# R210I.net
KiCad netlist of a schematic drawn in EAGLE
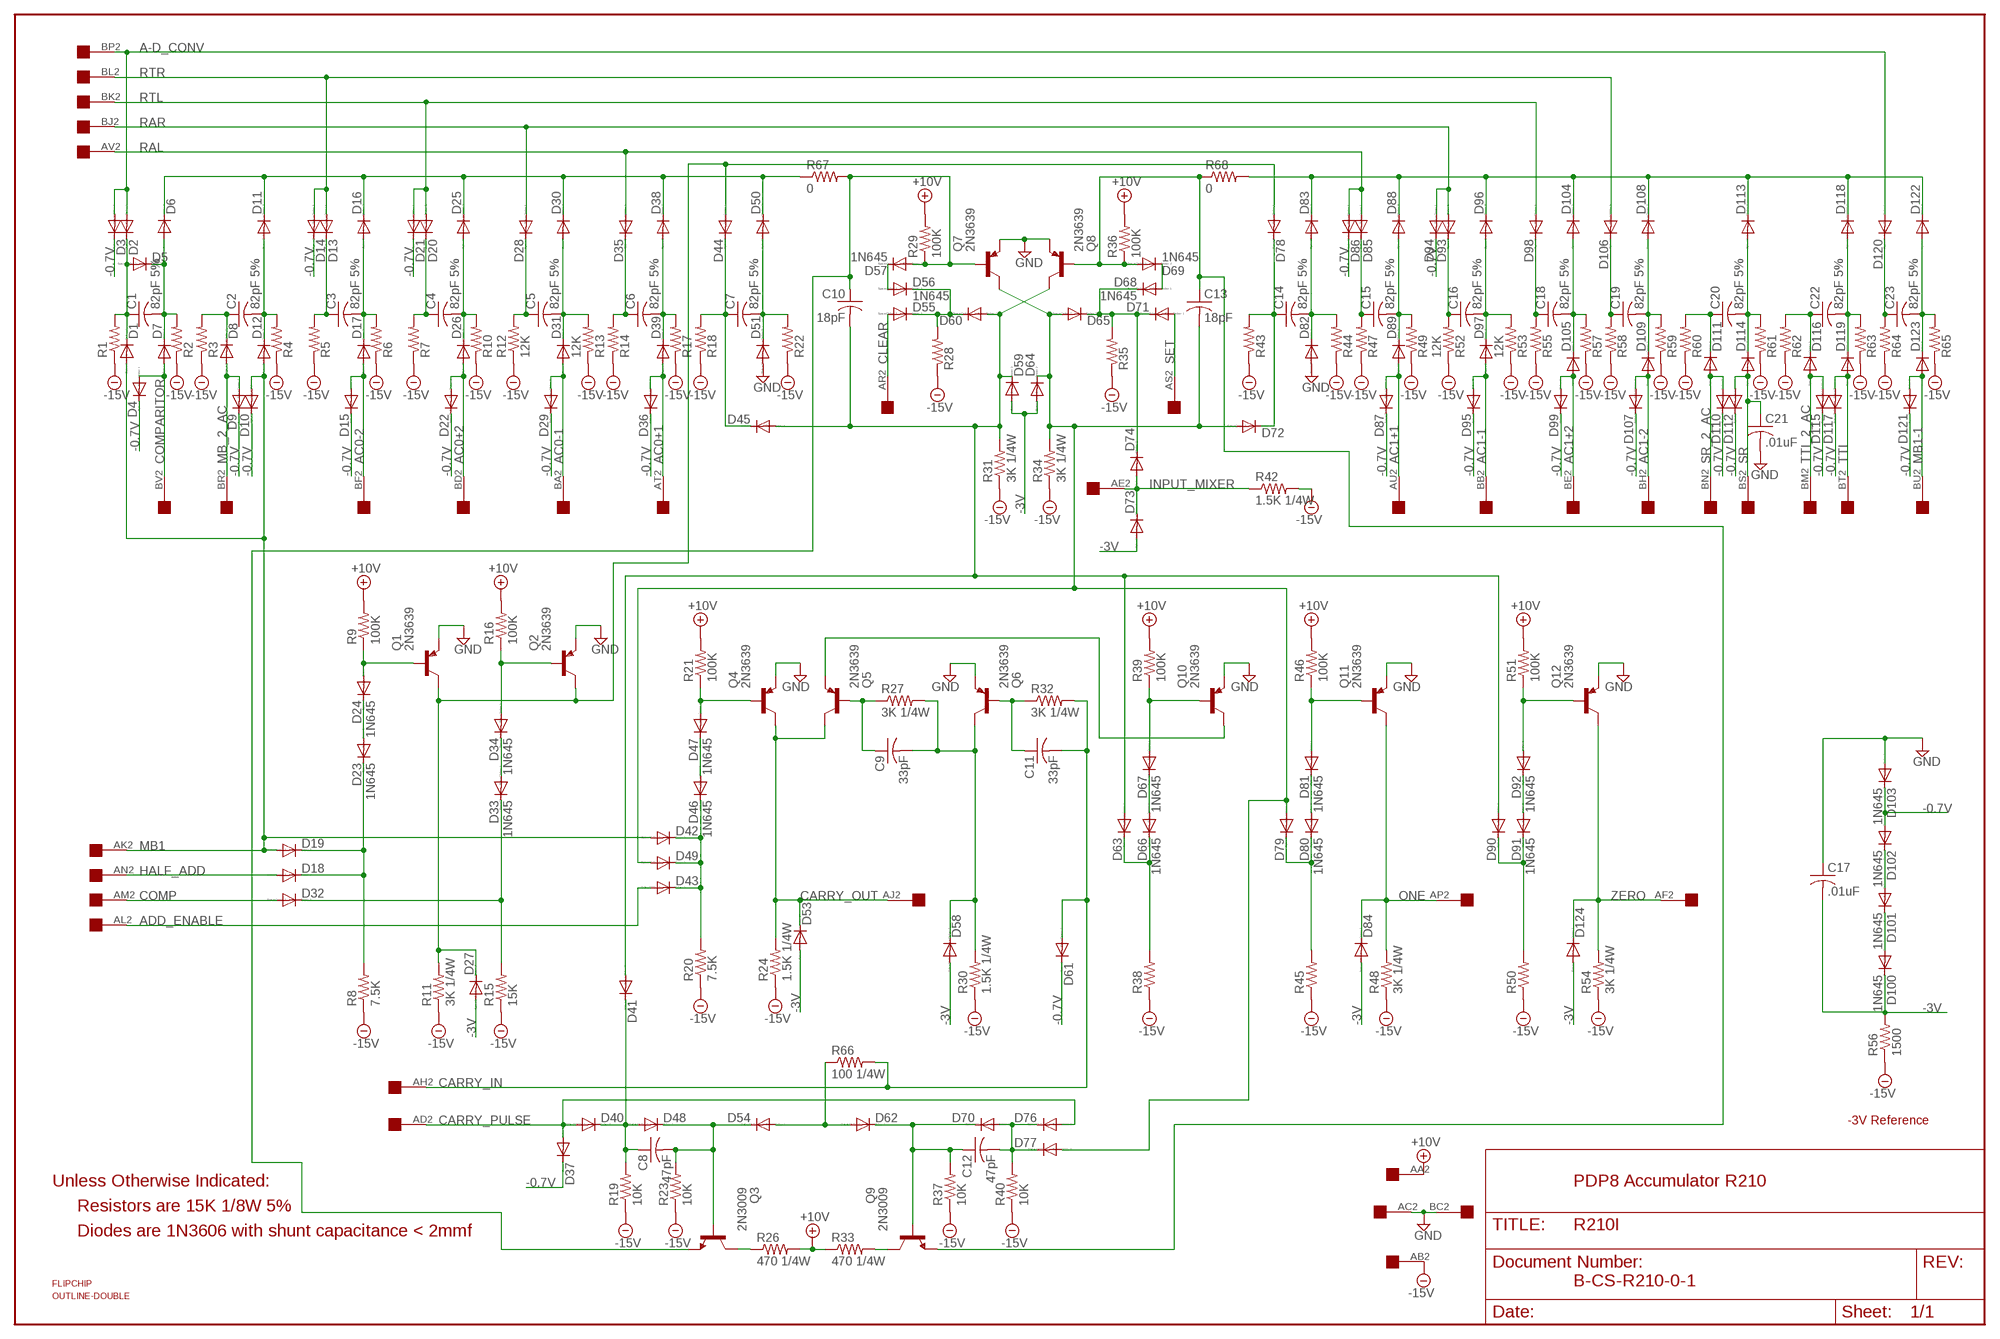
[diagram p0: schematic, sheet 1]

(export (version "E")
  (design (tool "Eeschema 10.0.6"))
  (components
    (comp (ref "C1")
      (value "82pF 5%")
      (footprint "eagle-import:C075-032X103")
      (libsource (lib "eagle-import") (part "C-US075-032X103"))
    )
    (comp (ref "C2")
      (value "82pF 5%")
      (footprint "eagle-import:C075-032X103")
      (libsource (lib "eagle-import") (part "C-US075-032X103"))
    )
    (comp (ref "C3")
      (value "82pF 5%")
      (footprint "eagle-import:C075-032X103")
      (libsource (lib "eagle-import") (part "C-US075-032X103"))
    )
    (comp (ref "C4")
      (value "82pF 5%")
      (footprint "eagle-import:C075-032X103")
      (libsource (lib "eagle-import") (part "C-US075-032X103"))
    )
    (comp (ref "C5")
      (value "82pF 5%")
      (footprint "eagle-import:C075-032X103")
      (libsource (lib "eagle-import") (part "C-US075-032X103"))
    )
    (comp (ref "C6")
      (value "82pF 5%")
      (footprint "eagle-import:C075-032X103")
      (libsource (lib "eagle-import") (part "C-US075-032X103"))
    )
    (comp (ref "C7")
      (value "82pF 5%")
      (footprint "eagle-import:C075-032X103")
      (libsource (lib "eagle-import") (part "C-US075-032X103"))
    )
    (comp (ref "C8")
      (value "47pF")
      (footprint "eagle-import:C075-032X103")
      (libsource (lib "eagle-import") (part "C-US075-032X103"))
    )
    (comp (ref "C9")
      (value "33pF")
      (footprint "eagle-import:C075-032X103")
      (libsource (lib "eagle-import") (part "C-US075-032X103"))
    )
    (comp (ref "C10")
      (value "18pF")
      (footprint "eagle-import:C075-032X103")
      (libsource (lib "eagle-import") (part "C-US075-032X103"))
    )
    (comp (ref "C11")
      (value "33pF")
      (footprint "eagle-import:C075-032X103")
      (libsource (lib "eagle-import") (part "C-US075-032X103"))
    )
    (comp (ref "C12")
      (value "47pF")
      (footprint "eagle-import:C075-032X103")
      (libsource (lib "eagle-import") (part "C-US075-032X103"))
    )
    (comp (ref "C13")
      (value "18pF")
      (footprint "eagle-import:C075-032X103")
      (libsource (lib "eagle-import") (part "C-US075-032X103"))
    )
    (comp (ref "C14")
      (value "82pF 5%")
      (footprint "eagle-import:C075-032X103")
      (libsource (lib "eagle-import") (part "C-US075-032X103"))
    )
    (comp (ref "C15")
      (value "82pF 5%")
      (footprint "eagle-import:C075-032X103")
      (libsource (lib "eagle-import") (part "C-US075-032X103"))
    )
    (comp (ref "C16")
      (value "82pF 5%")
      (footprint "eagle-import:C075-032X103")
      (libsource (lib "eagle-import") (part "C-US075-032X103"))
    )
    (comp (ref "C17")
      (value ".01uF")
      (footprint "eagle-import:C050-025X075")
      (libsource (lib "eagle-import") (part "C-US050-025X075"))
    )
    (comp (ref "C18")
      (value "82pF 5%")
      (footprint "eagle-import:C075-032X103")
      (libsource (lib "eagle-import") (part "C-US075-032X103"))
    )
    (comp (ref "C19")
      (value "82pF 5%")
      (footprint "eagle-import:C075-032X103")
      (libsource (lib "eagle-import") (part "C-US075-032X103"))
    )
    (comp (ref "C20")
      (value "82pF 5%")
      (footprint "eagle-import:C075-032X103")
      (libsource (lib "eagle-import") (part "C-US075-032X103"))
    )
    (comp (ref "C21")
      (value ".01uF")
      (footprint "eagle-import:C050-025X075")
      (libsource (lib "eagle-import") (part "C-US050-025X075"))
    )
    (comp (ref "C22")
      (value "82pF 5%")
      (footprint "eagle-import:C075-032X103")
      (libsource (lib "eagle-import") (part "C-US075-032X103"))
    )
    (comp (ref "C23")
      (value "82pF 5%")
      (footprint "eagle-import:C075-032X103")
      (libsource (lib "eagle-import") (part "C-US075-032X103"))
    )
    (comp (ref "D1")
      (value "1N4148DO35-10")
      (footprint "eagle-import:DO35-10")
      (libsource (lib "eagle-import") (part "1N4148DO35-10"))
    )
    (comp (ref "D2")
      (value "1N4148DO35-10")
      (footprint "eagle-import:DO35-10")
      (libsource (lib "eagle-import") (part "1N4148DO35-10"))
    )
    (comp (ref "D3")
      (value "1N4148DO35-10")
      (footprint "eagle-import:DO35-10")
      (libsource (lib "eagle-import") (part "1N4148DO35-10"))
    )
    (comp (ref "D4")
      (value "1N4148DO35-10")
      (footprint "eagle-import:DO35-10")
      (libsource (lib "eagle-import") (part "1N4148DO35-10"))
    )
    (comp (ref "D5")
      (value "1N4148DO35-10")
      (footprint "eagle-import:DO35-10")
      (libsource (lib "eagle-import") (part "1N4148DO35-10"))
    )
    (comp (ref "D6")
      (value "1N4148DO35-10")
      (footprint "eagle-import:DO35-10")
      (libsource (lib "eagle-import") (part "1N4148DO35-10"))
    )
    (comp (ref "D7")
      (value "1N4148DO35-10")
      (footprint "eagle-import:DO35-10")
      (libsource (lib "eagle-import") (part "1N4148DO35-10"))
    )
    (comp (ref "D8")
      (value "1N4148DO35-10")
      (footprint "eagle-import:DO35-10")
      (libsource (lib "eagle-import") (part "1N4148DO35-10"))
    )
    (comp (ref "D9")
      (value "1N4148DO35-10")
      (footprint "eagle-import:DO35-10")
      (libsource (lib "eagle-import") (part "1N4148DO35-10"))
    )
    (comp (ref "D10")
      (value "1N4148DO35-10")
      (footprint "eagle-import:DO35-10")
      (libsource (lib "eagle-import") (part "1N4148DO35-10"))
    )
    (comp (ref "D11")
      (value "1N4148DO35-10")
      (footprint "eagle-import:DO35-10")
      (libsource (lib "eagle-import") (part "1N4148DO35-10"))
    )
    (comp (ref "D12")
      (value "1N4148DO35-10")
      (footprint "eagle-import:DO35-10")
      (libsource (lib "eagle-import") (part "1N4148DO35-10"))
    )
    (comp (ref "D13")
      (value "1N4148DO35-10")
      (footprint "eagle-import:DO35-10")
      (libsource (lib "eagle-import") (part "1N4148DO35-10"))
    )
    (comp (ref "D14")
      (value "1N4148DO35-10")
      (footprint "eagle-import:DO35-10")
      (libsource (lib "eagle-import") (part "1N4148DO35-10"))
    )
    (comp (ref "D15")
      (value "1N4148DO35-10")
      (footprint "eagle-import:DO35-10")
      (libsource (lib "eagle-import") (part "1N4148DO35-10"))
    )
    (comp (ref "D16")
      (value "1N4148DO35-10")
      (footprint "eagle-import:DO35-10")
      (libsource (lib "eagle-import") (part "1N4148DO35-10"))
    )
    (comp (ref "D17")
      (value "1N4148DO35-10")
      (footprint "eagle-import:DO35-10")
      (libsource (lib "eagle-import") (part "1N4148DO35-10"))
    )
    (comp (ref "D18")
      (value "1N4148DO35-10")
      (footprint "eagle-import:DO35-10")
      (libsource (lib "eagle-import") (part "1N4148DO35-10"))
    )
    (comp (ref "D19")
      (value "1N4148DO35-10")
      (footprint "eagle-import:DO35-10")
      (libsource (lib "eagle-import") (part "1N4148DO35-10"))
    )
    (comp (ref "D20")
      (value "1N4148DO35-10")
      (footprint "eagle-import:DO35-10")
      (libsource (lib "eagle-import") (part "1N4148DO35-10"))
    )
    (comp (ref "D21")
      (value "1N4148DO35-10")
      (footprint "eagle-import:DO35-10")
      (libsource (lib "eagle-import") (part "1N4148DO35-10"))
    )
    (comp (ref "D22")
      (value "1N4148DO35-10")
      (footprint "eagle-import:DO35-10")
      (libsource (lib "eagle-import") (part "1N4148DO35-10"))
    )
    (comp (ref "D23")
      (value "1N645")
      (footprint "eagle-import:DO35-10")
      (libsource (lib "eagle-import") (part "1N4148DO35-10"))
    )
    (comp (ref "D24")
      (value "1N645")
      (footprint "eagle-import:DO35-10")
      (libsource (lib "eagle-import") (part "1N4148DO35-10"))
    )
    (comp (ref "D25")
      (value "1N4148DO35-10")
      (footprint "eagle-import:DO35-10")
      (libsource (lib "eagle-import") (part "1N4148DO35-10"))
    )
    (comp (ref "D26")
      (value "1N4148DO35-10")
      (footprint "eagle-import:DO35-10")
      (libsource (lib "eagle-import") (part "1N4148DO35-10"))
    )
    (comp (ref "D27")
      (value "1N4148DO35-10")
      (footprint "eagle-import:DO35-10")
      (libsource (lib "eagle-import") (part "1N4148DO35-10"))
    )
    (comp (ref "D28")
      (value "1N4148DO35-10")
      (footprint "eagle-import:DO35-10")
      (libsource (lib "eagle-import") (part "1N4148DO35-10"))
    )
    (comp (ref "D29")
      (value "1N4148DO35-10")
      (footprint "eagle-import:DO35-10")
      (libsource (lib "eagle-import") (part "1N4148DO35-10"))
    )
    (comp (ref "D30")
      (value "1N4148DO35-10")
      (footprint "eagle-import:DO35-10")
      (libsource (lib "eagle-import") (part "1N4148DO35-10"))
    )
    (comp (ref "D31")
      (value "1N4148DO35-10")
      (footprint "eagle-import:DO35-10")
      (libsource (lib "eagle-import") (part "1N4148DO35-10"))
    )
    (comp (ref "D32")
      (value "1N4148DO35-10")
      (footprint "eagle-import:DO35-10")
      (libsource (lib "eagle-import") (part "1N4148DO35-10"))
    )
    (comp (ref "D33")
      (value "1N645")
      (footprint "eagle-import:DO35-10")
      (libsource (lib "eagle-import") (part "1N4148DO35-10"))
    )
    (comp (ref "D34")
      (value "1N645")
      (footprint "eagle-import:DO35-10")
      (libsource (lib "eagle-import") (part "1N4148DO35-10"))
    )
    (comp (ref "D35")
      (value "1N4148DO35-10")
      (footprint "eagle-import:DO35-10")
      (libsource (lib "eagle-import") (part "1N4148DO35-10"))
    )
    (comp (ref "D36")
      (value "1N4148DO35-10")
      (footprint "eagle-import:DO35-10")
      (libsource (lib "eagle-import") (part "1N4148DO35-10"))
    )
    (comp (ref "D37")
      (value "1N4148DO35-10")
      (footprint "eagle-import:DO35-10")
      (libsource (lib "eagle-import") (part "1N4148DO35-10"))
    )
    (comp (ref "D38")
      (value "1N4148DO35-10")
      (footprint "eagle-import:DO35-10")
      (libsource (lib "eagle-import") (part "1N4148DO35-10"))
    )
    (comp (ref "D39")
      (value "1N4148DO35-10")
      (footprint "eagle-import:DO35-10")
      (libsource (lib "eagle-import") (part "1N4148DO35-10"))
    )
    (comp (ref "D40")
      (value "1N4148DO35-10")
      (footprint "eagle-import:DO35-10")
      (libsource (lib "eagle-import") (part "1N4148DO35-10"))
    )
    (comp (ref "D41")
      (value "1N4148DO35-10")
      (footprint "eagle-import:DO35-10")
      (libsource (lib "eagle-import") (part "1N4148DO35-10"))
    )
    (comp (ref "D42")
      (value "1N4148DO35-10")
      (footprint "eagle-import:DO35-10")
      (libsource (lib "eagle-import") (part "1N4148DO35-10"))
    )
    (comp (ref "D43")
      (value "1N4148DO35-10")
      (footprint "eagle-import:DO35-10")
      (libsource (lib "eagle-import") (part "1N4148DO35-10"))
    )
    (comp (ref "D44")
      (value "1N4148DO35-10")
      (footprint "eagle-import:DO35-10")
      (libsource (lib "eagle-import") (part "1N4148DO35-10"))
    )
    (comp (ref "D45")
      (value "1N4148DO35-10")
      (footprint "eagle-import:DO35-10")
      (libsource (lib "eagle-import") (part "1N4148DO35-10"))
    )
    (comp (ref "D46")
      (value "1N645")
      (footprint "eagle-import:DO35-10")
      (libsource (lib "eagle-import") (part "1N4148DO35-10"))
    )
    (comp (ref "D47")
      (value "1N645")
      (footprint "eagle-import:DO35-10")
      (libsource (lib "eagle-import") (part "1N4148DO35-10"))
    )
    (comp (ref "D48")
      (value "1N4148DO35-10")
      (footprint "eagle-import:DO35-10")
      (libsource (lib "eagle-import") (part "1N4148DO35-10"))
    )
    (comp (ref "D49")
      (value "1N4148DO35-10")
      (footprint "eagle-import:DO35-10")
      (libsource (lib "eagle-import") (part "1N4148DO35-10"))
    )
    (comp (ref "D50")
      (value "1N4148DO35-10")
      (footprint "eagle-import:DO35-10")
      (libsource (lib "eagle-import") (part "1N4148DO35-10"))
    )
    (comp (ref "D51")
      (value "1N4148DO35-10")
      (footprint "eagle-import:DO35-10")
      (libsource (lib "eagle-import") (part "1N4148DO35-10"))
    )
    (comp (ref "D53")
      (value "1N4148DO35-10")
      (footprint "eagle-import:DO35-10")
      (libsource (lib "eagle-import") (part "1N4148DO35-10"))
    )
    (comp (ref "D54")
      (value "1N4148DO35-10")
      (footprint "eagle-import:DO35-10")
      (libsource (lib "eagle-import") (part "1N4148DO35-10"))
    )
    (comp (ref "D55")
      (value "1N4148DO35-10")
      (footprint "eagle-import:DO35-10")
      (libsource (lib "eagle-import") (part "1N4148DO35-10"))
    )
    (comp (ref "D56")
      (value "1N645")
      (footprint "eagle-import:DO35-10")
      (libsource (lib "eagle-import") (part "1N4148DO35-10"))
    )
    (comp (ref "D57")
      (value "1N645")
      (footprint "eagle-import:DO35-10")
      (libsource (lib "eagle-import") (part "1N4148DO35-10"))
    )
    (comp (ref "D58")
      (value "1N4148DO35-10")
      (footprint "eagle-import:DO35-10")
      (libsource (lib "eagle-import") (part "1N4148DO35-10"))
    )
    (comp (ref "D59")
      (value "1N4148DO35-10")
      (footprint "eagle-import:DO35-10")
      (libsource (lib "eagle-import") (part "1N4148DO35-10"))
    )
    (comp (ref "D60")
      (value "1N4148DO35-10")
      (footprint "eagle-import:DO35-10")
      (libsource (lib "eagle-import") (part "1N4148DO35-10"))
    )
    (comp (ref "D61")
      (value "1N4148DO35-10")
      (footprint "eagle-import:DO35-10")
      (libsource (lib "eagle-import") (part "1N4148DO35-10"))
    )
    (comp (ref "D62")
      (value "1N4148DO35-10")
      (footprint "eagle-import:DO35-10")
      (libsource (lib "eagle-import") (part "1N4148DO35-10"))
    )
    (comp (ref "D63")
      (value "1N4148DO35-10")
      (footprint "eagle-import:DO35-10")
      (libsource (lib "eagle-import") (part "1N4148DO35-10"))
    )
    (comp (ref "D64")
      (value "1N4148DO35-10")
      (footprint "eagle-import:DO35-10")
      (libsource (lib "eagle-import") (part "1N4148DO35-10"))
    )
    (comp (ref "D65")
      (value "1N4148DO35-10")
      (footprint "eagle-import:DO35-10")
      (libsource (lib "eagle-import") (part "1N4148DO35-10"))
    )
    (comp (ref "D66")
      (value "1N645")
      (footprint "eagle-import:DO35-10")
      (libsource (lib "eagle-import") (part "1N4148DO35-10"))
    )
    (comp (ref "D67")
      (value "1N645")
      (footprint "eagle-import:DO35-10")
      (libsource (lib "eagle-import") (part "1N4148DO35-10"))
    )
    (comp (ref "D68")
      (value "1N645")
      (footprint "eagle-import:DO35-10")
      (libsource (lib "eagle-import") (part "1N4148DO35-10"))
    )
    (comp (ref "D69")
      (value "1N645")
      (footprint "eagle-import:DO35-10")
      (libsource (lib "eagle-import") (part "1N4148DO35-10"))
    )
    (comp (ref "D70")
      (value "1N4148DO35-10")
      (footprint "eagle-import:DO35-10")
      (libsource (lib "eagle-import") (part "1N4148DO35-10"))
    )
    (comp (ref "D71")
      (value "1N4148DO35-10")
      (footprint "eagle-import:DO35-10")
      (libsource (lib "eagle-import") (part "1N4148DO35-10"))
    )
    (comp (ref "D72")
      (value "1N4148DO35-10")
      (footprint "eagle-import:DO35-10")
      (libsource (lib "eagle-import") (part "1N4148DO35-10"))
    )
    (comp (ref "D73")
      (value "1N4148DO35-10")
      (footprint "eagle-import:DO35-10")
      (libsource (lib "eagle-import") (part "1N4148DO35-10"))
    )
    (comp (ref "D74")
      (value "1N4148DO35-10")
      (footprint "eagle-import:DO35-10")
      (libsource (lib "eagle-import") (part "1N4148DO35-10"))
    )
    (comp (ref "D76")
      (value "1N4148DO35-10")
      (footprint "eagle-import:DO35-10")
      (libsource (lib "eagle-import") (part "1N4148DO35-10"))
    )
    (comp (ref "D77")
      (value "1N4148DO35-10")
      (footprint "eagle-import:DO35-10")
      (libsource (lib "eagle-import") (part "1N4148DO35-10"))
    )
    (comp (ref "D78")
      (value "1N4148DO35-10")
      (footprint "eagle-import:DO35-10")
      (libsource (lib "eagle-import") (part "1N4148DO35-10"))
    )
    (comp (ref "D79")
      (value "1N4148DO35-10")
      (footprint "eagle-import:DO35-10")
      (libsource (lib "eagle-import") (part "1N4148DO35-10"))
    )
    (comp (ref "D80")
      (value "1N645")
      (footprint "eagle-import:DO35-10")
      (libsource (lib "eagle-import") (part "1N4148DO35-10"))
    )
    (comp (ref "D81")
      (value "1N645")
      (footprint "eagle-import:DO35-10")
      (libsource (lib "eagle-import") (part "1N4148DO35-10"))
    )
    (comp (ref "D82")
      (value "1N4148DO35-10")
      (footprint "eagle-import:DO35-10")
      (libsource (lib "eagle-import") (part "1N4148DO35-10"))
    )
    (comp (ref "D83")
      (value "1N4148DO35-10")
      (footprint "eagle-import:DO35-10")
      (libsource (lib "eagle-import") (part "1N4148DO35-10"))
    )
    (comp (ref "D84")
      (value "1N4148DO35-10")
      (footprint "eagle-import:DO35-10")
      (libsource (lib "eagle-import") (part "1N4148DO35-10"))
    )
    (comp (ref "D85")
      (value "1N4148DO35-10")
      (footprint "eagle-import:DO35-10")
      (libsource (lib "eagle-import") (part "1N4148DO35-10"))
    )
    (comp (ref "D86")
      (value "1N4148DO35-10")
      (footprint "eagle-import:DO35-10")
      (libsource (lib "eagle-import") (part "1N4148DO35-10"))
    )
    (comp (ref "D87")
      (value "1N4148DO35-10")
      (footprint "eagle-import:DO35-10")
      (libsource (lib "eagle-import") (part "1N4148DO35-10"))
    )
    (comp (ref "D88")
      (value "1N4148DO35-10")
      (footprint "eagle-import:DO35-10")
      (libsource (lib "eagle-import") (part "1N4148DO35-10"))
    )
    (comp (ref "D89")
      (value "1N4148DO35-10")
      (footprint "eagle-import:DO35-10")
      (libsource (lib "eagle-import") (part "1N4148DO35-10"))
    )
    (comp (ref "D90")
      (value "1N4148DO35-10")
      (footprint "eagle-import:DO35-10")
      (libsource (lib "eagle-import") (part "1N4148DO35-10"))
    )
    (comp (ref "D91")
      (value "1N645")
      (footprint "eagle-import:DO35-10")
      (libsource (lib "eagle-import") (part "1N4148DO35-10"))
    )
    (comp (ref "D92")
      (value "1N645")
      (footprint "eagle-import:DO35-10")
      (libsource (lib "eagle-import") (part "1N4148DO35-10"))
    )
    (comp (ref "D93")
      (value "1N4148DO35-10")
      (footprint "eagle-import:DO35-10")
      (libsource (lib "eagle-import") (part "1N4148DO35-10"))
    )
    (comp (ref "D94")
      (value "1N4148DO35-10")
      (footprint "eagle-import:DO35-10")
      (libsource (lib "eagle-import") (part "1N4148DO35-10"))
    )
    (comp (ref "D95")
      (value "1N4148DO35-10")
      (footprint "eagle-import:DO35-10")
      (libsource (lib "eagle-import") (part "1N4148DO35-10"))
    )
    (comp (ref "D96")
      (value "1N4148DO35-10")
      (footprint "eagle-import:DO35-10")
      (libsource (lib "eagle-import") (part "1N4148DO35-10"))
    )
    (comp (ref "D97")
      (value "1N4148DO35-10")
      (footprint "eagle-import:DO35-10")
      (libsource (lib "eagle-import") (part "1N4148DO35-10"))
    )
    (comp (ref "D98")
      (value "1N4148DO35-10")
      (footprint "eagle-import:DO35-10")
      (libsource (lib "eagle-import") (part "1N4148DO35-10"))
    )
    (comp (ref "D99")
      (value "1N4148DO35-10")
      (footprint "eagle-import:DO35-10")
      (libsource (lib "eagle-import") (part "1N4148DO35-10"))
    )
    (comp (ref "D100")
      (value "1N645")
      (footprint "eagle-import:DO35-10")
      (libsource (lib "eagle-import") (part "1N4148DO35-10"))
    )
    (comp (ref "D101")
      (value "1N645")
      (footprint "eagle-import:DO35-10")
      (libsource (lib "eagle-import") (part "1N4148DO35-10"))
    )
    (comp (ref "D102")
      (value "1N645")
      (footprint "eagle-import:DO35-10")
      (libsource (lib "eagle-import") (part "1N4148DO35-10"))
    )
    (comp (ref "D103")
      (value "1N645")
      (footprint "eagle-import:DO35-10")
      (libsource (lib "eagle-import") (part "1N4148DO35-10"))
    )
    (comp (ref "D104")
      (value "1N4148DO35-10")
      (footprint "eagle-import:DO35-10")
      (libsource (lib "eagle-import") (part "1N4148DO35-10"))
    )
    (comp (ref "D105")
      (value "1N4148DO35-10")
      (footprint "eagle-import:DO35-10")
      (libsource (lib "eagle-import") (part "1N4148DO35-10"))
    )
    (comp (ref "D106")
      (value "1N4148DO35-10")
      (footprint "eagle-import:DO35-10")
      (libsource (lib "eagle-import") (part "1N4148DO35-10"))
    )
    (comp (ref "D107")
      (value "1N4148DO35-10")
      (footprint "eagle-import:DO35-10")
      (libsource (lib "eagle-import") (part "1N4148DO35-10"))
    )
    (comp (ref "D108")
      (value "1N4148DO35-10")
      (footprint "eagle-import:DO35-10")
      (libsource (lib "eagle-import") (part "1N4148DO35-10"))
    )
    (comp (ref "D109")
      (value "1N4148DO35-10")
      (footprint "eagle-import:DO35-10")
      (libsource (lib "eagle-import") (part "1N4148DO35-10"))
    )
    (comp (ref "D110")
      (value "1N4148DO35-10")
      (footprint "eagle-import:DO35-10")
      (libsource (lib "eagle-import") (part "1N4148DO35-10"))
    )
    (comp (ref "D111")
      (value "1N4148DO35-10")
      (footprint "eagle-import:DO35-10")
      (libsource (lib "eagle-import") (part "1N4148DO35-10"))
    )
    (comp (ref "D112")
      (value "1N4148DO35-10")
      (footprint "eagle-import:DO35-10")
      (libsource (lib "eagle-import") (part "1N4148DO35-10"))
    )
    (comp (ref "D113")
      (value "1N4148DO35-10")
      (footprint "eagle-import:DO35-10")
      (libsource (lib "eagle-import") (part "1N4148DO35-10"))
    )
    (comp (ref "D114")
      (value "1N4148DO35-10")
      (footprint "eagle-import:DO35-10")
      (libsource (lib "eagle-import") (part "1N4148DO35-10"))
    )
    (comp (ref "D115")
      (value "1N4148DO35-10")
      (footprint "eagle-import:DO35-10")
      (libsource (lib "eagle-import") (part "1N4148DO35-10"))
    )
    (comp (ref "D116")
      (value "1N4148DO35-10")
      (footprint "eagle-import:DO35-10")
      (libsource (lib "eagle-import") (part "1N4148DO35-10"))
    )
    (comp (ref "D117")
      (value "1N4148DO35-10")
      (footprint "eagle-import:DO35-10")
      (libsource (lib "eagle-import") (part "1N4148DO35-10"))
    )
    (comp (ref "D118")
      (value "1N4148DO35-10")
      (footprint "eagle-import:DO35-10")
      (libsource (lib "eagle-import") (part "1N4148DO35-10"))
    )
    (comp (ref "D119")
      (value "1N4148DO35-10")
      (footprint "eagle-import:DO35-10")
      (libsource (lib "eagle-import") (part "1N4148DO35-10"))
    )
    (comp (ref "D120")
      (value "1N4148DO35-10")
      (footprint "eagle-import:DO35-10")
      (libsource (lib "eagle-import") (part "1N4148DO35-10"))
    )
    (comp (ref "D121")
      (value "1N4148DO35-10")
      (footprint "eagle-import:DO35-10")
      (libsource (lib "eagle-import") (part "1N4148DO35-10"))
    )
    (comp (ref "D122")
      (value "1N4148DO35-10")
      (footprint "eagle-import:DO35-10")
      (libsource (lib "eagle-import") (part "1N4148DO35-10"))
    )
    (comp (ref "D123")
      (value "1N4148DO35-10")
      (footprint "eagle-import:DO35-10")
      (libsource (lib "eagle-import") (part "1N4148DO35-10"))
    )
    (comp (ref "D124")
      (value "1N4148DO35-10")
      (footprint "eagle-import:DO35-10")
      (libsource (lib "eagle-import") (part "1N4148DO35-10"))
    )
    (comp (ref "Q1")
      (value "2N3639")
      (footprint "eagle-import:TO39")
      (libsource (lib "eagle-import") (part "2N3637"))
    )
    (comp (ref "Q2")
      (value "2N3639")
      (footprint "eagle-import:TO39")
      (libsource (lib "eagle-import") (part "2N3637"))
    )
    (comp (ref "Q3")
      (value "2N3009")
      (footprint "eagle-import:TO5")
      (libsource (lib "eagle-import") (part "2N2102"))
    )
    (comp (ref "Q4")
      (value "2N3639")
      (footprint "eagle-import:TO39")
      (libsource (lib "eagle-import") (part "2N3637"))
    )
    (comp (ref "Q5")
      (value "2N3639")
      (footprint "eagle-import:TO39")
      (libsource (lib "eagle-import") (part "2N3637"))
    )
    (comp (ref "Q6")
      (value "2N3639")
      (footprint "eagle-import:TO39")
      (libsource (lib "eagle-import") (part "2N3637"))
    )
    (comp (ref "Q7")
      (value "2N3639")
      (footprint "eagle-import:TO39")
      (libsource (lib "eagle-import") (part "2N3637"))
    )
    (comp (ref "Q8")
      (value "2N3639")
      (footprint "eagle-import:TO39")
      (libsource (lib "eagle-import") (part "2N3637"))
    )
    (comp (ref "Q9")
      (value "2N3009")
      (footprint "eagle-import:TO5")
      (libsource (lib "eagle-import") (part "2N2102"))
    )
    (comp (ref "Q10")
      (value "2N3639")
      (footprint "eagle-import:TO39")
      (libsource (lib "eagle-import") (part "2N3637"))
    )
    (comp (ref "Q11")
      (value "2N3639")
      (footprint "eagle-import:TO39")
      (libsource (lib "eagle-import") (part "2N3637"))
    )
    (comp (ref "Q12")
      (value "2N3639")
      (footprint "eagle-import:TO39")
      (libsource (lib "eagle-import") (part "2N3637"))
    )
    (comp (ref "R1")
      (value "R-US_0207/10")
      (footprint "eagle-import:0207_10")
      (libsource (lib "eagle-import") (part "R-US_0207/10"))
    )
    (comp (ref "R2")
      (value "R-US_0207/10")
      (footprint "eagle-import:0207_10")
      (libsource (lib "eagle-import") (part "R-US_0207/10"))
    )
    (comp (ref "R3")
      (value "R-US_0207/10")
      (footprint "eagle-import:0207_10")
      (libsource (lib "eagle-import") (part "R-US_0207/10"))
    )
    (comp (ref "R4")
      (value "R-US_0207/10")
      (footprint "eagle-import:0207_10")
      (libsource (lib "eagle-import") (part "R-US_0207/10"))
    )
    (comp (ref "R5")
      (value "R-US_0207/10")
      (footprint "eagle-import:0207_10")
      (libsource (lib "eagle-import") (part "R-US_0207/10"))
    )
    (comp (ref "R6")
      (value "R-US_0207/10")
      (footprint "eagle-import:0207_10")
      (libsource (lib "eagle-import") (part "R-US_0207/10"))
    )
    (comp (ref "R7")
      (value "R-US_0207/10")
      (footprint "eagle-import:0207_10")
      (libsource (lib "eagle-import") (part "R-US_0207/10"))
    )
    (comp (ref "R8")
      (value "7.5K")
      (footprint "eagle-import:0207_10")
      (libsource (lib "eagle-import") (part "R-US_0207/10"))
    )
    (comp (ref "R9")
      (value "100K")
      (footprint "eagle-import:0207_10")
      (libsource (lib "eagle-import") (part "R-US_0207/10"))
    )
    (comp (ref "R10")
      (value "R-US_0207/10")
      (footprint "eagle-import:0207_10")
      (libsource (lib "eagle-import") (part "R-US_0207/10"))
    )
    (comp (ref "R11")
      (value "3K 1/4W")
      (footprint "eagle-import:0207_10")
      (libsource (lib "eagle-import") (part "R-US_0207/10"))
    )
    (comp (ref "R12")
      (value "12K")
      (footprint "eagle-import:0207_10")
      (libsource (lib "eagle-import") (part "R-US_0207/10"))
    )
    (comp (ref "R13")
      (value "12K")
      (footprint "eagle-import:0207_10")
      (libsource (lib "eagle-import") (part "R-US_0207/10"))
    )
    (comp (ref "R14")
      (value "R-US_0207/10")
      (footprint "eagle-import:0207_10")
      (libsource (lib "eagle-import") (part "R-US_0207/10"))
    )
    (comp (ref "R15")
      (value "15K")
      (footprint "eagle-import:0207_10")
      (libsource (lib "eagle-import") (part "R-US_0207/10"))
    )
    (comp (ref "R16")
      (value "100K")
      (footprint "eagle-import:0207_10")
      (libsource (lib "eagle-import") (part "R-US_0207/10"))
    )
    (comp (ref "R17")
      (value "R-US_0207/10")
      (footprint "eagle-import:0207_10")
      (libsource (lib "eagle-import") (part "R-US_0207/10"))
    )
    (comp (ref "R18")
      (value "R-US_0207/10")
      (footprint "eagle-import:0207_10")
      (libsource (lib "eagle-import") (part "R-US_0207/10"))
    )
    (comp (ref "R19")
      (value "10K")
      (footprint "eagle-import:0207_10")
      (libsource (lib "eagle-import") (part "R-US_0207/10"))
    )
    (comp (ref "R20")
      (value "7.5K")
      (footprint "eagle-import:0207_10")
      (libsource (lib "eagle-import") (part "R-US_0207/10"))
    )
    (comp (ref "R21")
      (value "100K")
      (footprint "eagle-import:0207_10")
      (libsource (lib "eagle-import") (part "R-US_0207/10"))
    )
    (comp (ref "R22")
      (value "R-US_0207/10")
      (footprint "eagle-import:0207_10")
      (libsource (lib "eagle-import") (part "R-US_0207/10"))
    )
    (comp (ref "R23")
      (value "10K")
      (footprint "eagle-import:0207_10")
      (libsource (lib "eagle-import") (part "R-US_0207/10"))
    )
    (comp (ref "R24")
      (value "1.5K 1/4W")
      (footprint "eagle-import:0207_10")
      (libsource (lib "eagle-import") (part "R-US_0207/10"))
    )
    (comp (ref "R26")
      (value "470 1/4W")
      (footprint "eagle-import:0207_10")
      (libsource (lib "eagle-import") (part "R-US_0207/10"))
    )
    (comp (ref "R27")
      (value "3K 1/4W")
      (footprint "eagle-import:0207_10")
      (libsource (lib "eagle-import") (part "R-US_0207/10"))
    )
    (comp (ref "R28")
      (value "R-US_0207/10")
      (footprint "eagle-import:0207_10")
      (libsource (lib "eagle-import") (part "R-US_0207/10"))
    )
    (comp (ref "R29")
      (value "100K")
      (footprint "eagle-import:0207_10")
      (libsource (lib "eagle-import") (part "R-US_0207/10"))
    )
    (comp (ref "R30")
      (value "1.5K 1/4W")
      (footprint "eagle-import:0207_10")
      (libsource (lib "eagle-import") (part "R-US_0207/10"))
    )
    (comp (ref "R31")
      (value "3K 1/4W")
      (footprint "eagle-import:0207_10")
      (libsource (lib "eagle-import") (part "R-US_0207/10"))
    )
    (comp (ref "R32")
      (value "3K 1/4W")
      (footprint "eagle-import:0207_10")
      (libsource (lib "eagle-import") (part "R-US_0207/10"))
    )
    (comp (ref "R33")
      (value "470 1/4W")
      (footprint "eagle-import:0207_10")
      (libsource (lib "eagle-import") (part "R-US_0207/10"))
    )
    (comp (ref "R34")
      (value "3K 1/4W")
      (footprint "eagle-import:0207_10")
      (libsource (lib "eagle-import") (part "R-US_0207/10"))
    )
    (comp (ref "R35")
      (value "R-US_0207/10")
      (footprint "eagle-import:0207_10")
      (libsource (lib "eagle-import") (part "R-US_0207/10"))
    )
    (comp (ref "R36")
      (value "100K")
      (footprint "eagle-import:0207_10")
      (libsource (lib "eagle-import") (part "R-US_0207/10"))
    )
    (comp (ref "R37")
      (value "10K")
      (footprint "eagle-import:0207_10")
      (libsource (lib "eagle-import") (part "R-US_0207/10"))
    )
    (comp (ref "R38")
      (value "R-US_0207/10")
      (footprint "eagle-import:0207_10")
      (libsource (lib "eagle-import") (part "R-US_0207/10"))
    )
    (comp (ref "R39")
      (value "100K")
      (footprint "eagle-import:0207_10")
      (libsource (lib "eagle-import") (part "R-US_0207/10"))
    )
    (comp (ref "R40")
      (value "10K")
      (footprint "eagle-import:0207_10")
      (libsource (lib "eagle-import") (part "R-US_0207/10"))
    )
    (comp (ref "R42")
      (value "1.5K 1/4W")
      (footprint "eagle-import:0207_10")
      (libsource (lib "eagle-import") (part "R-US_0207/10"))
    )
    (comp (ref "R43")
      (value "R-US_0207/10")
      (footprint "eagle-import:0207_10")
      (libsource (lib "eagle-import") (part "R-US_0207/10"))
    )
    (comp (ref "R44")
      (value "R-US_0207/10")
      (footprint "eagle-import:0207_10")
      (libsource (lib "eagle-import") (part "R-US_0207/10"))
    )
    (comp (ref "R45")
      (value "R-US_0207/10")
      (footprint "eagle-import:0207_10")
      (libsource (lib "eagle-import") (part "R-US_0207/10"))
    )
    (comp (ref "R46")
      (value "100K")
      (footprint "eagle-import:0207_10")
      (libsource (lib "eagle-import") (part "R-US_0207/10"))
    )
    (comp (ref "R47")
      (value "R-US_0207/10")
      (footprint "eagle-import:0207_10")
      (libsource (lib "eagle-import") (part "R-US_0207/10"))
    )
    (comp (ref "R48")
      (value "3K 1/4W")
      (footprint "eagle-import:0207_10")
      (libsource (lib "eagle-import") (part "R-US_0207/10"))
    )
    (comp (ref "R49")
      (value "R-US_0207/10")
      (footprint "eagle-import:0207_10")
      (libsource (lib "eagle-import") (part "R-US_0207/10"))
    )
    (comp (ref "R50")
      (value "R-US_0207/10")
      (footprint "eagle-import:0207_10")
      (libsource (lib "eagle-import") (part "R-US_0207/10"))
    )
    (comp (ref "R51")
      (value "100K")
      (footprint "eagle-import:0207_10")
      (libsource (lib "eagle-import") (part "R-US_0207/10"))
    )
    (comp (ref "R52")
      (value "12K")
      (footprint "eagle-import:0207_10")
      (libsource (lib "eagle-import") (part "R-US_0207/10"))
    )
    (comp (ref "R53")
      (value "12K")
      (footprint "eagle-import:0207_10")
      (libsource (lib "eagle-import") (part "R-US_0207/10"))
    )
    (comp (ref "R54")
      (value "3K 1/4W")
      (footprint "eagle-import:0207_10")
      (libsource (lib "eagle-import") (part "R-US_0207/10"))
    )
    (comp (ref "R55")
      (value "R-US_0207/10")
      (footprint "eagle-import:0207_10")
      (libsource (lib "eagle-import") (part "R-US_0207/10"))
    )
    (comp (ref "R56")
      (value "1500")
      (footprint "eagle-import:0207_10")
      (libsource (lib "eagle-import") (part "R-US_0207/10"))
    )
    (comp (ref "R57")
      (value "R-US_0207/10")
      (footprint "eagle-import:0207_10")
      (libsource (lib "eagle-import") (part "R-US_0207/10"))
    )
    (comp (ref "R58")
      (value "R-US_0207/10")
      (footprint "eagle-import:0207_10")
      (libsource (lib "eagle-import") (part "R-US_0207/10"))
    )
    (comp (ref "R59")
      (value "R-US_0207/10")
      (footprint "eagle-import:0207_10")
      (libsource (lib "eagle-import") (part "R-US_0207/10"))
    )
    (comp (ref "R60")
      (value "R-US_0207/10")
      (footprint "eagle-import:0207_10")
      (libsource (lib "eagle-import") (part "R-US_0207/10"))
    )
    (comp (ref "R61")
      (value "R-US_0207/10")
      (footprint "eagle-import:0207_10")
      (libsource (lib "eagle-import") (part "R-US_0207/10"))
    )
    (comp (ref "R62")
      (value "R-US_0207/10")
      (footprint "eagle-import:0207_10")
      (libsource (lib "eagle-import") (part "R-US_0207/10"))
    )
    (comp (ref "R63")
      (value "R-US_0207/10")
      (footprint "eagle-import:0207_10")
      (libsource (lib "eagle-import") (part "R-US_0207/10"))
    )
    (comp (ref "R64")
      (value "R-US_0207/10")
      (footprint "eagle-import:0207_10")
      (libsource (lib "eagle-import") (part "R-US_0207/10"))
    )
    (comp (ref "R65")
      (value "R-US_0207/10")
      (footprint "eagle-import:0207_10")
      (libsource (lib "eagle-import") (part "R-US_0207/10"))
    )
    (comp (ref "R66")
      (value "100 1/4W")
      (footprint "eagle-import:0207_10")
      (libsource (lib "eagle-import") (part "R-US_0207/10"))
    )
    (comp (ref "R67")
      (value "0")
      (footprint "eagle-import:0207_10")
      (libsource (lib "eagle-import") (part "R-US_0207/10"))
    )
    (comp (ref "R68")
      (value "0")
      (footprint "eagle-import:0207_10")
      (libsource (lib "eagle-import") (part "R-US_0207/10"))
    )
    (comp (ref "U$1")
      (value "DOUBLE")
      (footprint "eagle-import:EDGE-CON4")
      (libsource (lib "eagle-import") (part "DOUBLE"))
    )
    (comp (ref "U$2")
      (value "FLIPCHIP")
      (footprint "eagle-import:FLIPCHIP")
      (libsource (lib "eagle-import") (part "FLIPCHIP"))
    )
    (comp (ref "U$3")
      (value "OUTLINE-DOUBLE")
      (footprint "eagle-import:DOUBLE")
      (libsource (lib "eagle-import") (part "OUTLINE-DOUBLE"))
    )
  )
  (nets
    (net (code "1") (name "+10V") (class "Default")
      (node (ref "R16") (pin "2") (pinfunction "2_2") (pintype "passive"))
      (node (ref "R21") (pin "2") (pinfunction "2_2") (pintype "passive"))
      (node (ref "R26") (pin "2") (pinfunction "2_2") (pintype "passive"))
      (node (ref "R29") (pin "2") (pinfunction "2_2") (pintype "passive"))
      (node (ref "R33") (pin "1") (pinfunction "1_1") (pintype "passive"))
      (node (ref "R36") (pin "2") (pinfunction "2_2") (pintype "passive"))
      (node (ref "R39") (pin "2") (pinfunction "2_2") (pintype "passive"))
      (node (ref "R46") (pin "2") (pinfunction "2_2") (pintype "passive"))
      (node (ref "R51") (pin "2") (pinfunction "2_2") (pintype "passive"))
      (node (ref "R9") (pin "2") (pinfunction "2_2") (pintype "passive"))
      (node (ref "U$1") (pin "AA2") (pinfunction "1_AA2") (pintype "bidirectional"))
    )
    (net (code "2") (name "-15V") (class "Default")
      (node (ref "R1") (pin "1") (pinfunction "1_1") (pintype "passive"))
      (node (ref "R10") (pin "1") (pinfunction "1_1") (pintype "passive"))
      (node (ref "R11") (pin "1") (pinfunction "1_1") (pintype "passive"))
      (node (ref "R12") (pin "1") (pinfunction "1_1") (pintype "passive"))
      (node (ref "R13") (pin "1") (pinfunction "1_1") (pintype "passive"))
      (node (ref "R14") (pin "1") (pinfunction "1_1") (pintype "passive"))
      (node (ref "R15") (pin "1") (pinfunction "1_1") (pintype "passive"))
      (node (ref "R17") (pin "1") (pinfunction "1_1") (pintype "passive"))
      (node (ref "R18") (pin "1") (pinfunction "1_1") (pintype "passive"))
      (node (ref "R19") (pin "1") (pinfunction "1_1") (pintype "passive"))
      (node (ref "R2") (pin "1") (pinfunction "1_1") (pintype "passive"))
      (node (ref "R20") (pin "1") (pinfunction "1_1") (pintype "passive"))
      (node (ref "R22") (pin "1") (pinfunction "1_1") (pintype "passive"))
      (node (ref "R23") (pin "1") (pinfunction "1_1") (pintype "passive"))
      (node (ref "R24") (pin "1") (pinfunction "1_1") (pintype "passive"))
      (node (ref "R28") (pin "1") (pinfunction "1_1") (pintype "passive"))
      (node (ref "R3") (pin "1") (pinfunction "1_1") (pintype "passive"))
      (node (ref "R30") (pin "1") (pinfunction "1_1") (pintype "passive"))
      (node (ref "R31") (pin "1") (pinfunction "1_1") (pintype "passive"))
      (node (ref "R34") (pin "1") (pinfunction "1_1") (pintype "passive"))
      (node (ref "R35") (pin "1") (pinfunction "1_1") (pintype "passive"))
      (node (ref "R37") (pin "1") (pinfunction "1_1") (pintype "passive"))
      (node (ref "R38") (pin "1") (pinfunction "1_1") (pintype "passive"))
      (node (ref "R4") (pin "1") (pinfunction "1_1") (pintype "passive"))
      (node (ref "R40") (pin "1") (pinfunction "1_1") (pintype "passive"))
      (node (ref "R42") (pin "2") (pinfunction "2_2") (pintype "passive"))
      (node (ref "R43") (pin "1") (pinfunction "1_1") (pintype "passive"))
      (node (ref "R44") (pin "1") (pinfunction "1_1") (pintype "passive"))
      (node (ref "R45") (pin "1") (pinfunction "1_1") (pintype "passive"))
      (node (ref "R47") (pin "1") (pinfunction "1_1") (pintype "passive"))
      (node (ref "R48") (pin "1") (pinfunction "1_1") (pintype "passive"))
      (node (ref "R49") (pin "1") (pinfunction "1_1") (pintype "passive"))
      (node (ref "R5") (pin "1") (pinfunction "1_1") (pintype "passive"))
      (node (ref "R50") (pin "1") (pinfunction "1_1") (pintype "passive"))
      (node (ref "R52") (pin "1") (pinfunction "1_1") (pintype "passive"))
      (node (ref "R53") (pin "1") (pinfunction "1_1") (pintype "passive"))
      (node (ref "R54") (pin "1") (pinfunction "1_1") (pintype "passive"))
      (node (ref "R55") (pin "1") (pinfunction "1_1") (pintype "passive"))
      (node (ref "R56") (pin "1") (pinfunction "1_1") (pintype "passive"))
      (node (ref "R57") (pin "1") (pinfunction "1_1") (pintype "passive"))
      (node (ref "R58") (pin "1") (pinfunction "1_1") (pintype "passive"))
      (node (ref "R59") (pin "1") (pinfunction "1_1") (pintype "passive"))
      (node (ref "R6") (pin "1") (pinfunction "1_1") (pintype "passive"))
      (node (ref "R60") (pin "1") (pinfunction "1_1") (pintype "passive"))
      (node (ref "R61") (pin "1") (pinfunction "1_1") (pintype "passive"))
      (node (ref "R62") (pin "1") (pinfunction "1_1") (pintype "passive"))
      (node (ref "R63") (pin "1") (pinfunction "1_1") (pintype "passive"))
      (node (ref "R64") (pin "1") (pinfunction "1_1") (pintype "passive"))
      (node (ref "R65") (pin "1") (pinfunction "1_1") (pintype "passive"))
      (node (ref "R7") (pin "1") (pinfunction "1_1") (pintype "passive"))
      (node (ref "R8") (pin "1") (pinfunction "1_1") (pintype "passive"))
      (node (ref "U$1") (pin "AB2") (pinfunction "1_AB2") (pintype "bidirectional"))
    )
    (net (code "3") (name "/-0.7V") (class "Default")
      (node (ref "D10") (pin "C") (pinfunction "C_C") (pintype "passive"))
      (node (ref "D102") (pin "A") (pinfunction "A_A") (pintype "passive"))
      (node (ref "D103") (pin "C") (pinfunction "C_C") (pintype "passive"))
      (node (ref "D107") (pin "C") (pinfunction "C_C") (pintype "passive"))
      (node (ref "D110") (pin "C") (pinfunction "C_C") (pintype "passive"))
      (node (ref "D112") (pin "C") (pinfunction "C_C") (pintype "passive"))
      (node (ref "D115") (pin "C") (pinfunction "C_C") (pintype "passive"))
      (node (ref "D117") (pin "C") (pinfunction "C_C") (pintype "passive"))
      (node (ref "D121") (pin "C") (pinfunction "C_C") (pintype "passive"))
      (node (ref "D14") (pin "C") (pinfunction "C_C") (pintype "passive"))
      (node (ref "D15") (pin "C") (pinfunction "C_C") (pintype "passive"))
      (node (ref "D21") (pin "C") (pinfunction "C_C") (pintype "passive"))
      (node (ref "D22") (pin "C") (pinfunction "C_C") (pintype "passive"))
      (node (ref "D29") (pin "C") (pinfunction "C_C") (pintype "passive"))
      (node (ref "D3") (pin "C") (pinfunction "C_C") (pintype "passive"))
      (node (ref "D36") (pin "C") (pinfunction "C_C") (pintype "passive"))
      (node (ref "D37") (pin "C") (pinfunction "C_C") (pintype "passive"))
      (node (ref "D4") (pin "C") (pinfunction "C_C") (pintype "passive"))
      (node (ref "D61") (pin "C") (pinfunction "C_C") (pintype "passive"))
      (node (ref "D86") (pin "C") (pinfunction "C_C") (pintype "passive"))
      (node (ref "D87") (pin "C") (pinfunction "C_C") (pintype "passive"))
      (node (ref "D9") (pin "C") (pinfunction "C_C") (pintype "passive"))
      (node (ref "D94") (pin "C") (pinfunction "C_C") (pintype "passive"))
      (node (ref "D95") (pin "C") (pinfunction "C_C") (pintype "passive"))
      (node (ref "D99") (pin "C") (pinfunction "C_C") (pintype "passive"))
    )
    (net (code "4") (name "/-3V") (class "Default")
      (node (ref "C17") (pin "2") (pinfunction "2_2") (pintype "passive"))
      (node (ref "D100") (pin "C") (pinfunction "C_C") (pintype "passive"))
      (node (ref "D124") (pin "A") (pinfunction "A_A") (pintype "passive"))
      (node (ref "D27") (pin "A") (pinfunction "A_A") (pintype "passive"))
      (node (ref "D53") (pin "A") (pinfunction "A_A") (pintype "passive"))
      (node (ref "D58") (pin "A") (pinfunction "A_A") (pintype "passive"))
      (node (ref "D59") (pin "A") (pinfunction "A_A") (pintype "passive"))
      (node (ref "D64") (pin "A") (pinfunction "A_A") (pintype "passive"))
      (node (ref "D73") (pin "A") (pinfunction "A_A") (pintype "passive"))
      (node (ref "D84") (pin "A") (pinfunction "A_A") (pintype "passive"))
      (node (ref "R56") (pin "2") (pinfunction "2_2") (pintype "passive"))
    )
    (net (code "5") (name "/A-D_CONV") (class "Default")
      (node (ref "D120") (pin "A") (pinfunction "A_A") (pintype "passive"))
      (node (ref "D2") (pin "A") (pinfunction "A_A") (pintype "passive"))
      (node (ref "D3") (pin "A") (pinfunction "A_A") (pintype "passive"))
      (node (ref "U$1") (pin "BP2") (pinfunction "1_BP2") (pintype "bidirectional"))
    )
    (net (code "6") (name "/AC0+1") (class "Default")
      (node (ref "D36") (pin "A") (pinfunction "A_A") (pintype "passive"))
      (node (ref "D39") (pin "A") (pinfunction "A_A") (pintype "passive"))
      (node (ref "U$1") (pin "AT2") (pinfunction "1_AT2") (pintype "bidirectional"))
    )
    (net (code "7") (name "/AC0+2") (class "Default")
      (node (ref "D22") (pin "A") (pinfunction "A_A") (pintype "passive"))
      (node (ref "D26") (pin "A") (pinfunction "A_A") (pintype "passive"))
      (node (ref "U$1") (pin "BD2") (pinfunction "1_BD2") (pintype "bidirectional"))
    )
    (net (code "8") (name "/AC0-1") (class "Default")
      (node (ref "D29") (pin "A") (pinfunction "A_A") (pintype "passive"))
      (node (ref "D31") (pin "A") (pinfunction "A_A") (pintype "passive"))
      (node (ref "U$1") (pin "BA2") (pinfunction "1_BA2") (pintype "bidirectional"))
    )
    (net (code "9") (name "/AC0-2") (class "Default")
      (node (ref "D15") (pin "A") (pinfunction "A_A") (pintype "passive"))
      (node (ref "D17") (pin "A") (pinfunction "A_A") (pintype "passive"))
      (node (ref "U$1") (pin "BF2") (pinfunction "1_BF2") (pintype "bidirectional"))
    )
    (net (code "10") (name "/AC1+1") (class "Default")
      (node (ref "D87") (pin "A") (pinfunction "A_A") (pintype "passive"))
      (node (ref "D89") (pin "A") (pinfunction "A_A") (pintype "passive"))
      (node (ref "U$1") (pin "AU2") (pinfunction "1_AU2") (pintype "bidirectional"))
    )
    (net (code "11") (name "/AC1+2") (class "Default")
      (node (ref "D105") (pin "A") (pinfunction "A_A") (pintype "passive"))
      (node (ref "D99") (pin "A") (pinfunction "A_A") (pintype "passive"))
      (node (ref "U$1") (pin "BE2") (pinfunction "1_BE2") (pintype "bidirectional"))
    )
    (net (code "12") (name "/AC1-1") (class "Default")
      (node (ref "D95") (pin "A") (pinfunction "A_A") (pintype "passive"))
      (node (ref "D97") (pin "A") (pinfunction "A_A") (pintype "passive"))
      (node (ref "U$1") (pin "BB2") (pinfunction "1_BB2") (pintype "bidirectional"))
    )
    (net (code "13") (name "/AC1-2") (class "Default")
      (node (ref "D107") (pin "A") (pinfunction "A_A") (pintype "passive"))
      (node (ref "D109") (pin "A") (pinfunction "A_A") (pintype "passive"))
      (node (ref "U$1") (pin "BH2") (pinfunction "1_BH2") (pintype "bidirectional"))
    )
    (net (code "14") (name "/ADD_ENABLE") (class "Default")
      (node (ref "D43") (pin "A") (pinfunction "A_A") (pintype "passive"))
      (node (ref "U$1") (pin "AL2") (pinfunction "1_AL2") (pintype "bidirectional"))
    )
    (net (code "15") (name "/CARRY_IN") (class "Default")
      (node (ref "C11") (pin "2") (pinfunction "2_2") (pintype "passive"))
      (node (ref "D61") (pin "A") (pinfunction "A_A") (pintype "passive"))
      (node (ref "R32") (pin "2") (pinfunction "2_2") (pintype "passive"))
      (node (ref "R66") (pin "2") (pinfunction "2_2") (pintype "passive"))
      (node (ref "U$1") (pin "AH2") (pinfunction "1_AH2") (pintype "bidirectional"))
    )
    (net (code "16") (name "/CARRY_OUT") (class "Default")
      (node (ref "D53") (pin "C") (pinfunction "C_C") (pintype "passive"))
      (node (ref "Q4") (pin "3") (pinfunction "C_3") (pintype "passive"))
      (node (ref "Q5") (pin "3") (pinfunction "C_3") (pintype "passive"))
      (node (ref "R24") (pin "2") (pinfunction "2_2") (pintype "passive"))
      (node (ref "U$1") (pin "AJ2") (pinfunction "1_AJ2") (pintype "bidirectional"))
    )
    (net (code "17") (name "/CARRY_PULSE") (class "Default")
      (node (ref "D37") (pin "A") (pinfunction "A_A") (pintype "passive"))
      (node (ref "D40") (pin "A") (pinfunction "A_A") (pintype "passive"))
      (node (ref "D76") (pin "A") (pinfunction "A_A") (pintype "passive"))
      (node (ref "U$1") (pin "AD2") (pinfunction "1_AD2") (pintype "bidirectional"))
    )
    (net (code "18") (name "/CLEAR") (class "Default")
      (node (ref "D55") (pin "A") (pinfunction "A_A") (pintype "passive"))
      (node (ref "U$1") (pin "AR2") (pinfunction "1_AR2") (pintype "bidirectional"))
    )
    (net (code "19") (name "/COMP") (class "Default")
      (node (ref "D32") (pin "A") (pinfunction "A_A") (pintype "passive"))
      (node (ref "U$1") (pin "AM2") (pinfunction "1_AM2") (pintype "bidirectional"))
    )
    (net (code "20") (name "/COMPARITOR") (class "Default")
      (node (ref "D4") (pin "A") (pinfunction "A_A") (pintype "passive"))
      (node (ref "D7") (pin "A") (pinfunction "A_A") (pintype "passive"))
      (node (ref "U$1") (pin "BV2") (pinfunction "1_BV2") (pintype "bidirectional"))
    )
    (net (code "21") (name "/HALF_ADD") (class "Default")
      (node (ref "D18") (pin "A") (pinfunction "A_A") (pintype "passive"))
      (node (ref "U$1") (pin "AN2") (pinfunction "1_AN2") (pintype "bidirectional"))
    )
    (net (code "22") (name "/INPUT_MIXER") (class "Default")
      (node (ref "D73") (pin "C") (pinfunction "C_C") (pintype "passive"))
      (node (ref "D74") (pin "A") (pinfunction "A_A") (pintype "passive"))
      (node (ref "R42") (pin "1") (pinfunction "1_1") (pintype "passive"))
      (node (ref "U$1") (pin "AE2") (pinfunction "1_AE2") (pintype "bidirectional"))
    )
    (net (code "23") (name "/MB1") (class "Default")
      (node (ref "D1") (pin "A") (pinfunction "A_A") (pintype "passive"))
      (node (ref "D10") (pin "A") (pinfunction "A_A") (pintype "passive"))
      (node (ref "D12") (pin "A") (pinfunction "A_A") (pintype "passive"))
      (node (ref "D19") (pin "A") (pinfunction "A_A") (pintype "passive"))
      (node (ref "D42") (pin "A") (pinfunction "A_A") (pintype "passive"))
      (node (ref "U$1") (pin "AK2") (pinfunction "1_AK2") (pintype "bidirectional"))
    )
    (net (code "24") (name "/MB1-1") (class "Default")
      (node (ref "D121") (pin "A") (pinfunction "A_A") (pintype "passive"))
      (node (ref "D123") (pin "A") (pinfunction "A_A") (pintype "passive"))
      (node (ref "U$1") (pin "BU2") (pinfunction "1_BU2") (pintype "bidirectional"))
    )
    (net (code "25") (name "/MB_2_AC") (class "Default")
      (node (ref "D8") (pin "A") (pinfunction "A_A") (pintype "passive"))
      (node (ref "D9") (pin "A") (pinfunction "A_A") (pintype "passive"))
      (node (ref "U$1") (pin "BR2") (pinfunction "1_BR2") (pintype "bidirectional"))
    )
    (net (code "26") (name "/ONE") (class "Default")
      (node (ref "D84") (pin "C") (pinfunction "C_C") (pintype "passive"))
      (node (ref "Q11") (pin "3") (pinfunction "C_3") (pintype "passive"))
      (node (ref "R48") (pin "2") (pinfunction "2_2") (pintype "passive"))
      (node (ref "U$1") (pin "AP2") (pinfunction "1_AP2") (pintype "bidirectional"))
    )
    (net (code "27") (name "/RAL") (class "Default")
      (node (ref "D35") (pin "A") (pinfunction "A_A") (pintype "passive"))
      (node (ref "D85") (pin "A") (pinfunction "A_A") (pintype "passive"))
      (node (ref "D86") (pin "A") (pinfunction "A_A") (pintype "passive"))
      (node (ref "U$1") (pin "AV2") (pinfunction "1_AV2") (pintype "bidirectional"))
    )
    (net (code "28") (name "/RAR") (class "Default")
      (node (ref "D28") (pin "A") (pinfunction "A_A") (pintype "passive"))
      (node (ref "D93") (pin "A") (pinfunction "A_A") (pintype "passive"))
      (node (ref "D94") (pin "A") (pinfunction "A_A") (pintype "passive"))
      (node (ref "U$1") (pin "BJ2") (pinfunction "1_BJ2") (pintype "bidirectional"))
    )
    (net (code "29") (name "/RTL") (class "Default")
      (node (ref "D20") (pin "A") (pinfunction "A_A") (pintype "passive"))
      (node (ref "D21") (pin "A") (pinfunction "A_A") (pintype "passive"))
      (node (ref "D98") (pin "A") (pinfunction "A_A") (pintype "passive"))
      (node (ref "U$1") (pin "BK2") (pinfunction "1_BK2") (pintype "bidirectional"))
    )
    (net (code "30") (name "/RTR") (class "Default")
      (node (ref "D106") (pin "A") (pinfunction "A_A") (pintype "passive"))
      (node (ref "D13") (pin "A") (pinfunction "A_A") (pintype "passive"))
      (node (ref "D14") (pin "A") (pinfunction "A_A") (pintype "passive"))
      (node (ref "U$1") (pin "BL2") (pinfunction "1_BL2") (pintype "bidirectional"))
    )
    (net (code "31") (name "/SET") (class "Default")
      (node (ref "D71") (pin "A") (pinfunction "A_A") (pintype "passive"))
      (node (ref "U$1") (pin "AS2") (pinfunction "1_AS2") (pintype "bidirectional"))
    )
    (net (code "32") (name "/SR") (class "Default")
      (node (ref "C21") (pin "1") (pinfunction "1_1") (pintype "passive"))
      (node (ref "D112") (pin "A") (pinfunction "A_A") (pintype "passive"))
      (node (ref "D114") (pin "A") (pinfunction "A_A") (pintype "passive"))
      (node (ref "U$1") (pin "BS2") (pinfunction "1_BS2") (pintype "bidirectional"))
    )
    (net (code "33") (name "/SR_2_AC") (class "Default")
      (node (ref "D110") (pin "A") (pinfunction "A_A") (pintype "passive"))
      (node (ref "D111") (pin "A") (pinfunction "A_A") (pintype "passive"))
      (node (ref "U$1") (pin "BN2") (pinfunction "1_BN2") (pintype "bidirectional"))
    )
    (net (code "34") (name "/TTI") (class "Default")
      (node (ref "D117") (pin "A") (pinfunction "A_A") (pintype "passive"))
      (node (ref "D119") (pin "A") (pinfunction "A_A") (pintype "passive"))
      (node (ref "U$1") (pin "BT2") (pinfunction "1_BT2") (pintype "bidirectional"))
    )
    (net (code "35") (name "/TTI_2_AC") (class "Default")
      (node (ref "D115") (pin "A") (pinfunction "A_A") (pintype "passive"))
      (node (ref "D116") (pin "A") (pinfunction "A_A") (pintype "passive"))
      (node (ref "U$1") (pin "BM2") (pinfunction "1_BM2") (pintype "bidirectional"))
    )
    (net (code "36") (name "/ZERO") (class "Default")
      (node (ref "D124") (pin "C") (pinfunction "C_C") (pintype "passive"))
      (node (ref "Q12") (pin "3") (pinfunction "C_3") (pintype "passive"))
      (node (ref "R54") (pin "2") (pinfunction "2_2") (pintype "passive"))
      (node (ref "U$1") (pin "AF2") (pinfunction "1_AF2") (pintype "bidirectional"))
    )
    (net (code "37") (name "GND") (class "Default")
      (node (ref "C17") (pin "1") (pinfunction "1_1") (pintype "passive"))
      (node (ref "C21") (pin "2") (pinfunction "2_2") (pintype "passive"))
      (node (ref "D103") (pin "A") (pinfunction "A_A") (pintype "passive"))
      (node (ref "D51") (pin "A") (pinfunction "A_A") (pintype "passive"))
      (node (ref "D82") (pin "A") (pinfunction "A_A") (pintype "passive"))
      (node (ref "Q1") (pin "1") (pinfunction "E_1") (pintype "passive"))
      (node (ref "Q10") (pin "1") (pinfunction "E_1") (pintype "passive"))
      (node (ref "Q11") (pin "1") (pinfunction "E_1") (pintype "passive"))
      (node (ref "Q12") (pin "1") (pinfunction "E_1") (pintype "passive"))
      (node (ref "Q2") (pin "1") (pinfunction "E_1") (pintype "passive"))
      (node (ref "Q4") (pin "1") (pinfunction "E_1") (pintype "passive"))
      (node (ref "Q6") (pin "1") (pinfunction "E_1") (pintype "passive"))
      (node (ref "Q7") (pin "1") (pinfunction "E_1") (pintype "passive"))
      (node (ref "Q8") (pin "1") (pinfunction "E_1") (pintype "passive"))
      (node (ref "U$1") (pin "AC2") (pinfunction "1_AC2") (pintype "bidirectional"))
      (node (ref "U$1") (pin "BC2") (pinfunction "1_BC2") (pintype "bidirectional"))
    )
    (net (code "38") (name "Net-(C1-Pad1)") (class "Default")
      (node (ref "C1") (pin "1") (pinfunction "1_1") (pintype "passive"))
      (node (ref "D1") (pin "C") (pinfunction "C_C") (pintype "passive"))
      (node (ref "D2") (pin "C") (pinfunction "C_C") (pintype "passive"))
      (node (ref "D5") (pin "A") (pinfunction "A_A") (pintype "passive"))
      (node (ref "R1") (pin "2") (pinfunction "2_2") (pintype "passive"))
    )
    (net (code "39") (name "Net-(C1-Pad2)") (class "Default")
      (node (ref "C1") (pin "2") (pinfunction "2_2") (pintype "passive"))
      (node (ref "D5") (pin "C") (pinfunction "C_C") (pintype "passive"))
      (node (ref "D6") (pin "A") (pinfunction "A_A") (pintype "passive"))
      (node (ref "D7") (pin "C") (pinfunction "C_C") (pintype "passive"))
      (node (ref "R2") (pin "2") (pinfunction "2_2") (pintype "passive"))
    )
    (net (code "40") (name "Net-(C2-Pad1)") (class "Default")
      (node (ref "C2") (pin "1") (pinfunction "1_1") (pintype "passive"))
      (node (ref "D8") (pin "C") (pinfunction "C_C") (pintype "passive"))
      (node (ref "R3") (pin "2") (pinfunction "2_2") (pintype "passive"))
    )
    (net (code "41") (name "Net-(C2-Pad2)") (class "Default")
      (node (ref "C2") (pin "2") (pinfunction "2_2") (pintype "passive"))
      (node (ref "D11") (pin "A") (pinfunction "A_A") (pintype "passive"))
      (node (ref "D12") (pin "C") (pinfunction "C_C") (pintype "passive"))
      (node (ref "R4") (pin "2") (pinfunction "2_2") (pintype "passive"))
    )
    (net (code "42") (name "Net-(C3-Pad1)") (class "Default")
      (node (ref "C3") (pin "1") (pinfunction "1_1") (pintype "passive"))
      (node (ref "D13") (pin "C") (pinfunction "C_C") (pintype "passive"))
      (node (ref "R5") (pin "2") (pinfunction "2_2") (pintype "passive"))
    )
    (net (code "43") (name "Net-(C3-Pad2)") (class "Default")
      (node (ref "C3") (pin "2") (pinfunction "2_2") (pintype "passive"))
      (node (ref "D16") (pin "A") (pinfunction "A_A") (pintype "passive"))
      (node (ref "D17") (pin "C") (pinfunction "C_C") (pintype "passive"))
      (node (ref "R6") (pin "2") (pinfunction "2_2") (pintype "passive"))
    )
    (net (code "44") (name "Net-(C4-Pad1)") (class "Default")
      (node (ref "C4") (pin "1") (pinfunction "1_1") (pintype "passive"))
      (node (ref "D20") (pin "C") (pinfunction "C_C") (pintype "passive"))
      (node (ref "R7") (pin "2") (pinfunction "2_2") (pintype "passive"))
    )
    (net (code "45") (name "Net-(C4-Pad2)") (class "Default")
      (node (ref "C4") (pin "2") (pinfunction "2_2") (pintype "passive"))
      (node (ref "D25") (pin "A") (pinfunction "A_A") (pintype "passive"))
      (node (ref "D26") (pin "C") (pinfunction "C_C") (pintype "passive"))
      (node (ref "R10") (pin "2") (pinfunction "2_2") (pintype "passive"))
    )
    (net (code "46") (name "Net-(C5-Pad1)") (class "Default")
      (node (ref "C5") (pin "1") (pinfunction "1_1") (pintype "passive"))
      (node (ref "D28") (pin "C") (pinfunction "C_C") (pintype "passive"))
      (node (ref "R12") (pin "2") (pinfunction "2_2") (pintype "passive"))
    )
    (net (code "47") (name "Net-(C5-Pad2)") (class "Default")
      (node (ref "C5") (pin "2") (pinfunction "2_2") (pintype "passive"))
      (node (ref "D30") (pin "A") (pinfunction "A_A") (pintype "passive"))
      (node (ref "D31") (pin "C") (pinfunction "C_C") (pintype "passive"))
      (node (ref "R13") (pin "2") (pinfunction "2_2") (pintype "passive"))
    )
    (net (code "48") (name "Net-(C6-Pad1)") (class "Default")
      (node (ref "C6") (pin "1") (pinfunction "1_1") (pintype "passive"))
      (node (ref "D35") (pin "C") (pinfunction "C_C") (pintype "passive"))
      (node (ref "R14") (pin "2") (pinfunction "2_2") (pintype "passive"))
    )
    (net (code "49") (name "Net-(C6-Pad2)") (class "Default")
      (node (ref "C6") (pin "2") (pinfunction "2_2") (pintype "passive"))
      (node (ref "D38") (pin "A") (pinfunction "A_A") (pintype "passive"))
      (node (ref "D39") (pin "C") (pinfunction "C_C") (pintype "passive"))
      (node (ref "R17") (pin "2") (pinfunction "2_2") (pintype "passive"))
    )
    (net (code "50") (name "Net-(C7-Pad1)") (class "Default")
      (node (ref "C7") (pin "1") (pinfunction "1_1") (pintype "passive"))
      (node (ref "D44") (pin "C") (pinfunction "C_C") (pintype "passive"))
      (node (ref "D45") (pin "C") (pinfunction "C_C") (pintype "passive"))
      (node (ref "R18") (pin "2") (pinfunction "2_2") (pintype "passive"))
    )
    (net (code "51") (name "Net-(C7-Pad2)") (class "Default")
      (node (ref "C7") (pin "2") (pinfunction "2_2") (pintype "passive"))
      (node (ref "D50") (pin "A") (pinfunction "A_A") (pintype "passive"))
      (node (ref "D51") (pin "C") (pinfunction "C_C") (pintype "passive"))
      (node (ref "R22") (pin "2") (pinfunction "2_2") (pintype "passive"))
    )
    (net (code "52") (name "Net-(C8-Pad1)") (class "Default")
      (node (ref "C8") (pin "1") (pinfunction "1_1") (pintype "passive"))
      (node (ref "D40") (pin "C") (pinfunction "C_C") (pintype "passive"))
      (node (ref "D41") (pin "C") (pinfunction "C_C") (pintype "passive"))
      (node (ref "D48") (pin "A") (pinfunction "A_A") (pintype "passive"))
      (node (ref "R19") (pin "2") (pinfunction "2_2") (pintype "passive"))
    )
    (net (code "53") (name "Net-(C12-Pad2)") (class "Default")
      (node (ref "C12") (pin "2") (pinfunction "2_2") (pintype "passive"))
      (node (ref "D70") (pin "A") (pinfunction "A_A") (pintype "passive"))
      (node (ref "D76") (pin "C") (pinfunction "C_C") (pintype "passive"))
      (node (ref "D77") (pin "C") (pinfunction "C_C") (pintype "passive"))
      (node (ref "R40") (pin "2") (pinfunction "2_2") (pintype "passive"))
    )
    (net (code "54") (name "Net-(C14-Pad1)") (class "Default")
      (node (ref "C14") (pin "1") (pinfunction "1_1") (pintype "passive"))
      (node (ref "D72") (pin "C") (pinfunction "C_C") (pintype "passive"))
      (node (ref "D78") (pin "C") (pinfunction "C_C") (pintype "passive"))
      (node (ref "R43") (pin "2") (pinfunction "2_2") (pintype "passive"))
    )
    (net (code "55") (name "Net-(C14-Pad2)") (class "Default")
      (node (ref "C14") (pin "2") (pinfunction "2_2") (pintype "passive"))
      (node (ref "D82") (pin "C") (pinfunction "C_C") (pintype "passive"))
      (node (ref "D83") (pin "A") (pinfunction "A_A") (pintype "passive"))
      (node (ref "R44") (pin "2") (pinfunction "2_2") (pintype "passive"))
    )
    (net (code "56") (name "Net-(C15-Pad1)") (class "Default")
      (node (ref "C15") (pin "1") (pinfunction "1_1") (pintype "passive"))
      (node (ref "D85") (pin "C") (pinfunction "C_C") (pintype "passive"))
      (node (ref "R47") (pin "2") (pinfunction "2_2") (pintype "passive"))
    )
    (net (code "57") (name "Net-(C15-Pad2)") (class "Default")
      (node (ref "C15") (pin "2") (pinfunction "2_2") (pintype "passive"))
      (node (ref "D88") (pin "A") (pinfunction "A_A") (pintype "passive"))
      (node (ref "D89") (pin "C") (pinfunction "C_C") (pintype "passive"))
      (node (ref "R49") (pin "2") (pinfunction "2_2") (pintype "passive"))
    )
    (net (code "58") (name "Net-(C16-Pad1)") (class "Default")
      (node (ref "C16") (pin "1") (pinfunction "1_1") (pintype "passive"))
      (node (ref "D93") (pin "C") (pinfunction "C_C") (pintype "passive"))
      (node (ref "R52") (pin "2") (pinfunction "2_2") (pintype "passive"))
    )
    (net (code "59") (name "Net-(C16-Pad2)") (class "Default")
      (node (ref "C16") (pin "2") (pinfunction "2_2") (pintype "passive"))
      (node (ref "D96") (pin "A") (pinfunction "A_A") (pintype "passive"))
      (node (ref "D97") (pin "C") (pinfunction "C_C") (pintype "passive"))
      (node (ref "R53") (pin "2") (pinfunction "2_2") (pintype "passive"))
    )
    (net (code "60") (name "Net-(C18-Pad1)") (class "Default")
      (node (ref "C18") (pin "1") (pinfunction "1_1") (pintype "passive"))
      (node (ref "D98") (pin "C") (pinfunction "C_C") (pintype "passive"))
      (node (ref "R55") (pin "2") (pinfunction "2_2") (pintype "passive"))
    )
    (net (code "61") (name "Net-(C18-Pad2)") (class "Default")
      (node (ref "C18") (pin "2") (pinfunction "2_2") (pintype "passive"))
      (node (ref "D104") (pin "A") (pinfunction "A_A") (pintype "passive"))
      (node (ref "D105") (pin "C") (pinfunction "C_C") (pintype "passive"))
      (node (ref "R57") (pin "2") (pinfunction "2_2") (pintype "passive"))
    )
    (net (code "62") (name "Net-(C19-Pad1)") (class "Default")
      (node (ref "C19") (pin "1") (pinfunction "1_1") (pintype "passive"))
      (node (ref "D106") (pin "C") (pinfunction "C_C") (pintype "passive"))
      (node (ref "R58") (pin "2") (pinfunction "2_2") (pintype "passive"))
    )
    (net (code "63") (name "Net-(C19-Pad2)") (class "Default")
      (node (ref "C19") (pin "2") (pinfunction "2_2") (pintype "passive"))
      (node (ref "D108") (pin "A") (pinfunction "A_A") (pintype "passive"))
      (node (ref "D109") (pin "C") (pinfunction "C_C") (pintype "passive"))
      (node (ref "R59") (pin "2") (pinfunction "2_2") (pintype "passive"))
    )
    (net (code "64") (name "Net-(C20-Pad1)") (class "Default")
      (node (ref "C20") (pin "1") (pinfunction "1_1") (pintype "passive"))
      (node (ref "D111") (pin "C") (pinfunction "C_C") (pintype "passive"))
      (node (ref "R60") (pin "2") (pinfunction "2_2") (pintype "passive"))
    )
    (net (code "65") (name "Net-(C20-Pad2)") (class "Default")
      (node (ref "C20") (pin "2") (pinfunction "2_2") (pintype "passive"))
      (node (ref "D113") (pin "A") (pinfunction "A_A") (pintype "passive"))
      (node (ref "D114") (pin "C") (pinfunction "C_C") (pintype "passive"))
      (node (ref "R61") (pin "2") (pinfunction "2_2") (pintype "passive"))
    )
    (net (code "66") (name "Net-(C22-Pad1)") (class "Default")
      (node (ref "C22") (pin "1") (pinfunction "1_1") (pintype "passive"))
      (node (ref "D116") (pin "C") (pinfunction "C_C") (pintype "passive"))
      (node (ref "R62") (pin "2") (pinfunction "2_2") (pintype "passive"))
    )
    (net (code "67") (name "Net-(C22-Pad2)") (class "Default")
      (node (ref "C22") (pin "2") (pinfunction "2_2") (pintype "passive"))
      (node (ref "D118") (pin "A") (pinfunction "A_A") (pintype "passive"))
      (node (ref "D119") (pin "C") (pinfunction "C_C") (pintype "passive"))
      (node (ref "R63") (pin "2") (pinfunction "2_2") (pintype "passive"))
    )
    (net (code "68") (name "Net-(C23-Pad1)") (class "Default")
      (node (ref "C23") (pin "1") (pinfunction "1_1") (pintype "passive"))
      (node (ref "D120") (pin "C") (pinfunction "C_C") (pintype "passive"))
      (node (ref "R64") (pin "2") (pinfunction "2_2") (pintype "passive"))
    )
    (net (code "69") (name "Net-(C23-Pad2)") (class "Default")
      (node (ref "C23") (pin "2") (pinfunction "2_2") (pintype "passive"))
      (node (ref "D122") (pin "A") (pinfunction "A_A") (pintype "passive"))
      (node (ref "D123") (pin "C") (pinfunction "C_C") (pintype "passive"))
      (node (ref "R65") (pin "2") (pinfunction "2_2") (pintype "passive"))
    )
    (net (code "70") (name "Net-(D11-PadC)") (class "Default")
      (node (ref "D11") (pin "C") (pinfunction "C_C") (pintype "passive"))
      (node (ref "D16") (pin "C") (pinfunction "C_C") (pintype "passive"))
      (node (ref "D25") (pin "C") (pinfunction "C_C") (pintype "passive"))
      (node (ref "D30") (pin "C") (pinfunction "C_C") (pintype "passive"))
      (node (ref "D38") (pin "C") (pinfunction "C_C") (pintype "passive"))
      (node (ref "D50") (pin "C") (pinfunction "C_C") (pintype "passive"))
      (node (ref "D6") (pin "C") (pinfunction "C_C") (pintype "passive"))
      (node (ref "R67") (pin "1") (pinfunction "1_1") (pintype "passive"))
    )
    (net (code "71") (name "Net-(D18-PadC)") (class "Default")
      (node (ref "D18") (pin "C") (pinfunction "C_C") (pintype "passive"))
      (node (ref "D19") (pin "C") (pinfunction "C_C") (pintype "passive"))
      (node (ref "D23") (pin "C") (pinfunction "C_C") (pintype "passive"))
      (node (ref "R8") (pin "2") (pinfunction "2_2") (pintype "passive"))
    )
    (net (code "72") (name "Net-(D23-PadA)") (class "Default")
      (node (ref "D23") (pin "A") (pinfunction "A_A") (pintype "passive"))
      (node (ref "D24") (pin "C") (pinfunction "C_C") (pintype "passive"))
    )
    (net (code "73") (name "Net-(D32-PadC)") (class "Default")
      (node (ref "D32") (pin "C") (pinfunction "C_C") (pintype "passive"))
      (node (ref "D33") (pin "C") (pinfunction "C_C") (pintype "passive"))
      (node (ref "R15") (pin "2") (pinfunction "2_2") (pintype "passive"))
    )
    (net (code "74") (name "Net-(D33-PadA)") (class "Default")
      (node (ref "D33") (pin "A") (pinfunction "A_A") (pintype "passive"))
      (node (ref "D34") (pin "C") (pinfunction "C_C") (pintype "passive"))
    )
    (net (code "75") (name "Net-(D42-PadC)") (class "Default")
      (node (ref "D42") (pin "C") (pinfunction "C_C") (pintype "passive"))
      (node (ref "D43") (pin "C") (pinfunction "C_C") (pintype "passive"))
      (node (ref "D46") (pin "C") (pinfunction "C_C") (pintype "passive"))
      (node (ref "D49") (pin "C") (pinfunction "C_C") (pintype "passive"))
      (node (ref "R20") (pin "2") (pinfunction "2_2") (pintype "passive"))
    )
    (net (code "76") (name "Net-(D46-PadA)") (class "Default")
      (node (ref "D46") (pin "A") (pinfunction "A_A") (pintype "passive"))
      (node (ref "D47") (pin "C") (pinfunction "C_C") (pintype "passive"))
    )
    (net (code "77") (name "Net-(D54-PadA)") (class "Default")
      (node (ref "D54") (pin "A") (pinfunction "A_A") (pintype "passive"))
      (node (ref "D62") (pin "A") (pinfunction "A_A") (pintype "passive"))
      (node (ref "R66") (pin "1") (pinfunction "1_1") (pintype "passive"))
    )
    (net (code "78") (name "Net-(D55-PadC)") (class "Default")
      (node (ref "D55") (pin "C") (pinfunction "C_C") (pintype "passive"))
      (node (ref "D56") (pin "C") (pinfunction "C_C") (pintype "passive"))
      (node (ref "D60") (pin "C") (pinfunction "C_C") (pintype "passive"))
      (node (ref "R28") (pin "2") (pinfunction "2_2") (pintype "passive"))
    )
    (net (code "79") (name "Net-(D56-PadA)") (class "Default")
      (node (ref "D56") (pin "A") (pinfunction "A_A") (pintype "passive"))
      (node (ref "D57") (pin "C") (pinfunction "C_C") (pintype "passive"))
    )
    (net (code "80") (name "Net-(D63-PadC)") (class "Default")
      (node (ref "D63") (pin "C") (pinfunction "C_C") (pintype "passive"))
      (node (ref "D66") (pin "C") (pinfunction "C_C") (pintype "passive"))
      (node (ref "R38") (pin "2") (pinfunction "2_2") (pintype "passive"))
    )
    (net (code "81") (name "Net-(D65-PadC)") (class "Default")
      (node (ref "D65") (pin "C") (pinfunction "C_C") (pintype "passive"))
      (node (ref "D68") (pin "C") (pinfunction "C_C") (pintype "passive"))
      (node (ref "D71") (pin "C") (pinfunction "C_C") (pintype "passive"))
      (node (ref "D74") (pin "C") (pinfunction "C_C") (pintype "passive"))
      (node (ref "R35") (pin "2") (pinfunction "2_2") (pintype "passive"))
    )
    (net (code "82") (name "Net-(D66-PadA)") (class "Default")
      (node (ref "D66") (pin "A") (pinfunction "A_A") (pintype "passive"))
      (node (ref "D67") (pin "C") (pinfunction "C_C") (pintype "passive"))
    )
    (net (code "83") (name "Net-(D68-PadA)") (class "Default")
      (node (ref "D68") (pin "A") (pinfunction "A_A") (pintype "passive"))
      (node (ref "D69") (pin "C") (pinfunction "C_C") (pintype "passive"))
    )
    (net (code "84") (name "Net-(D79-PadC)") (class "Default")
      (node (ref "D79") (pin "C") (pinfunction "C_C") (pintype "passive"))
      (node (ref "D80") (pin "C") (pinfunction "C_C") (pintype "passive"))
      (node (ref "R45") (pin "2") (pinfunction "2_2") (pintype "passive"))
    )
    (net (code "85") (name "Net-(D80-PadA)") (class "Default")
      (node (ref "D80") (pin "A") (pinfunction "A_A") (pintype "passive"))
      (node (ref "D81") (pin "C") (pinfunction "C_C") (pintype "passive"))
    )
    (net (code "86") (name "Net-(D90-PadC)") (class "Default")
      (node (ref "D90") (pin "C") (pinfunction "C_C") (pintype "passive"))
      (node (ref "D91") (pin "C") (pinfunction "C_C") (pintype "passive"))
      (node (ref "R50") (pin "2") (pinfunction "2_2") (pintype "passive"))
    )
    (net (code "87") (name "Net-(D91-PadA)") (class "Default")
      (node (ref "D91") (pin "A") (pinfunction "A_A") (pintype "passive"))
      (node (ref "D92") (pin "C") (pinfunction "C_C") (pintype "passive"))
    )
    (net (code "88") (name "Net-(D100-PadA)") (class "Default")
      (node (ref "D100") (pin "A") (pinfunction "A_A") (pintype "passive"))
      (node (ref "D101") (pin "C") (pinfunction "C_C") (pintype "passive"))
    )
    (net (code "89") (name "Net-(D101-PadA)") (class "Default")
      (node (ref "D101") (pin "A") (pinfunction "A_A") (pintype "passive"))
      (node (ref "D102") (pin "C") (pinfunction "C_C") (pintype "passive"))
    )
    (net (code "90") (name "Net-(D104-PadC)") (class "Default")
      (node (ref "D104") (pin "C") (pinfunction "C_C") (pintype "passive"))
      (node (ref "D108") (pin "C") (pinfunction "C_C") (pintype "passive"))
      (node (ref "D113") (pin "C") (pinfunction "C_C") (pintype "passive"))
      (node (ref "D118") (pin "C") (pinfunction "C_C") (pintype "passive"))
      (node (ref "D122") (pin "C") (pinfunction "C_C") (pintype "passive"))
      (node (ref "D83") (pin "C") (pinfunction "C_C") (pintype "passive"))
      (node (ref "D88") (pin "C") (pinfunction "C_C") (pintype "passive"))
      (node (ref "D96") (pin "C") (pinfunction "C_C") (pintype "passive"))
      (node (ref "R68") (pin "2") (pinfunction "2_2") (pintype "passive"))
    )
    (net (code "91") (name "Net-(Q1-B)") (class "Default")
      (node (ref "D24") (pin "A") (pinfunction "A_A") (pintype "passive"))
      (node (ref "Q1") (pin "2") (pinfunction "B_2") (pintype "passive"))
      (node (ref "R9") (pin "1") (pinfunction "1_1") (pintype "passive"))
    )
    (net (code "92") (name "Net-(Q1-C)") (class "Default")
      (node (ref "D27") (pin "C") (pinfunction "C_C") (pintype "passive"))
      (node (ref "D44") (pin "A") (pinfunction "A_A") (pintype "passive"))
      (node (ref "D78") (pin "A") (pinfunction "A_A") (pintype "passive"))
      (node (ref "Q1") (pin "3") (pinfunction "C_3") (pintype "passive"))
      (node (ref "Q2") (pin "3") (pinfunction "C_3") (pintype "passive"))
      (node (ref "R11") (pin "2") (pinfunction "2_2") (pintype "passive"))
    )
    (net (code "93") (name "Net-(Q2-B)") (class "Default")
      (node (ref "D34") (pin "A") (pinfunction "A_A") (pintype "passive"))
      (node (ref "Q2") (pin "2") (pinfunction "B_2") (pintype "passive"))
      (node (ref "R16") (pin "1") (pinfunction "1_1") (pintype "passive"))
    )
    (net (code "94") (name "Net-(Q3-B)") (class "Default")
      (node (ref "C8") (pin "2") (pinfunction "2_2") (pintype "passive"))
      (node (ref "D48") (pin "C") (pinfunction "C_C") (pintype "passive"))
      (node (ref "D54") (pin "C") (pinfunction "C_C") (pintype "passive"))
      (node (ref "Q3") (pin "2") (pinfunction "B_2") (pintype "passive"))
      (node (ref "R23") (pin "2") (pinfunction "2_2") (pintype "passive"))
    )
    (net (code "95") (name "Net-(Q3-C)") (class "Default")
      (node (ref "Q3") (pin "3") (pinfunction "C_3") (pintype "passive"))
      (node (ref "R26") (pin "1") (pinfunction "1_1") (pintype "passive"))
    )
    (net (code "96") (name "Net-(Q3-E)") (class "Default")
      (node (ref "C10") (pin "1") (pinfunction "1_1") (pintype "passive"))
      (node (ref "D57") (pin "A") (pinfunction "A_A") (pintype "passive"))
      (node (ref "Q3") (pin "1") (pinfunction "E_1") (pintype "passive"))
      (node (ref "Q7") (pin "2") (pinfunction "B_2") (pintype "passive"))
      (node (ref "R29") (pin "1") (pinfunction "1_1") (pintype "passive"))
      (node (ref "R67") (pin "2") (pinfunction "2_2") (pintype "passive"))
    )
    (net (code "97") (name "Net-(Q4-B)") (class "Default")
      (node (ref "D47") (pin "A") (pinfunction "A_A") (pintype "passive"))
      (node (ref "Q4") (pin "2") (pinfunction "B_2") (pintype "passive"))
      (node (ref "R21") (pin "1") (pinfunction "1_1") (pintype "passive"))
    )
    (net (code "98") (name "Net-(Q5-B)") (class "Default")
      (node (ref "C9") (pin "1") (pinfunction "1_1") (pintype "passive"))
      (node (ref "Q5") (pin "2") (pinfunction "B_2") (pintype "passive"))
      (node (ref "R27") (pin "1") (pinfunction "1_1") (pintype "passive"))
    )
    (net (code "99") (name "Net-(Q6-B)") (class "Default")
      (node (ref "C11") (pin "1") (pinfunction "1_1") (pintype "passive"))
      (node (ref "Q6") (pin "2") (pinfunction "B_2") (pintype "passive"))
      (node (ref "R32") (pin "1") (pinfunction "1_1") (pintype "passive"))
    )
    (net (code "100") (name "Net-(Q6-C)") (class "Default")
      (node (ref "C9") (pin "2") (pinfunction "2_2") (pintype "passive"))
      (node (ref "D58") (pin "C") (pinfunction "C_C") (pintype "passive"))
      (node (ref "Q6") (pin "3") (pinfunction "C_3") (pintype "passive"))
      (node (ref "R27") (pin "2") (pinfunction "2_2") (pintype "passive"))
      (node (ref "R30") (pin "2") (pinfunction "2_2") (pintype "passive"))
    )
    (net (code "101") (name "Net-(Q7-C)") (class "Default")
      (node (ref "C13") (pin "2") (pinfunction "2_2") (pintype "passive"))
      (node (ref "D49") (pin "A") (pinfunction "A_A") (pintype "passive"))
      (node (ref "D64") (pin "C") (pinfunction "C_C") (pintype "passive"))
      (node (ref "D65") (pin "A") (pinfunction "A_A") (pintype "passive"))
      (node (ref "D72") (pin "A") (pinfunction "A_A") (pintype "passive"))
      (node (ref "D77") (pin "A") (pinfunction "A_A") (pintype "passive"))
      (node (ref "D79") (pin "A") (pinfunction "A_A") (pintype "passive"))
      (node (ref "Q7") (pin "3") (pinfunction "C_3") (pintype "passive"))
      (node (ref "R34") (pin "2") (pinfunction "2_2") (pintype "passive"))
    )
    (net (code "102") (name "Net-(Q8-B)") (class "Default")
      (node (ref "C13") (pin "1") (pinfunction "1_1") (pintype "passive"))
      (node (ref "D69") (pin "A") (pinfunction "A_A") (pintype "passive"))
      (node (ref "Q8") (pin "2") (pinfunction "B_2") (pintype "passive"))
      (node (ref "Q9") (pin "1") (pinfunction "E_1") (pintype "passive"))
      (node (ref "R36") (pin "1") (pinfunction "1_1") (pintype "passive"))
      (node (ref "R68") (pin "1") (pinfunction "1_1") (pintype "passive"))
    )
    (net (code "103") (name "Net-(Q8-C)") (class "Default")
      (node (ref "C10") (pin "2") (pinfunction "2_2") (pintype "passive"))
      (node (ref "D41") (pin "A") (pinfunction "A_A") (pintype "passive"))
      (node (ref "D45") (pin "A") (pinfunction "A_A") (pintype "passive"))
      (node (ref "D59") (pin "C") (pinfunction "C_C") (pintype "passive"))
      (node (ref "D60") (pin "A") (pinfunction "A_A") (pintype "passive"))
      (node (ref "D63") (pin "A") (pinfunction "A_A") (pintype "passive"))
      (node (ref "D90") (pin "A") (pinfunction "A_A") (pintype "passive"))
      (node (ref "Q8") (pin "3") (pinfunction "C_3") (pintype "passive"))
      (node (ref "R31") (pin "2") (pinfunction "2_2") (pintype "passive"))
    )
    (net (code "104") (name "Net-(Q9-B)") (class "Default")
      (node (ref "C12") (pin "1") (pinfunction "1_1") (pintype "passive"))
      (node (ref "D62") (pin "C") (pinfunction "C_C") (pintype "passive"))
      (node (ref "D70") (pin "C") (pinfunction "C_C") (pintype "passive"))
      (node (ref "Q9") (pin "2") (pinfunction "B_2") (pintype "passive"))
      (node (ref "R37") (pin "2") (pinfunction "2_2") (pintype "passive"))
    )
    (net (code "105") (name "Net-(Q9-C)") (class "Default")
      (node (ref "Q9") (pin "3") (pinfunction "C_3") (pintype "passive"))
      (node (ref "R33") (pin "2") (pinfunction "2_2") (pintype "passive"))
    )
    (net (code "106") (name "Net-(Q10-B)") (class "Default")
      (node (ref "D67") (pin "A") (pinfunction "A_A") (pintype "passive"))
      (node (ref "Q10") (pin "2") (pinfunction "B_2") (pintype "passive"))
      (node (ref "R39") (pin "1") (pinfunction "1_1") (pintype "passive"))
    )
    (net (code "107") (name "Net-(Q10-C)") (class "Default")
      (node (ref "Q10") (pin "3") (pinfunction "C_3") (pintype "passive"))
      (node (ref "Q5") (pin "1") (pinfunction "E_1") (pintype "passive"))
    )
    (net (code "108") (name "Net-(Q11-B)") (class "Default")
      (node (ref "D81") (pin "A") (pinfunction "A_A") (pintype "passive"))
      (node (ref "Q11") (pin "2") (pinfunction "B_2") (pintype "passive"))
      (node (ref "R46") (pin "1") (pinfunction "1_1") (pintype "passive"))
    )
    (net (code "109") (name "Net-(Q12-B)") (class "Default")
      (node (ref "D92") (pin "A") (pinfunction "A_A") (pintype "passive"))
      (node (ref "Q12") (pin "2") (pinfunction "B_2") (pintype "passive"))
      (node (ref "R51") (pin "1") (pinfunction "1_1") (pintype "passive"))
    )
  )
)
